# Analog.net
KiCad netlist of a schematic drawn in Altium Designer
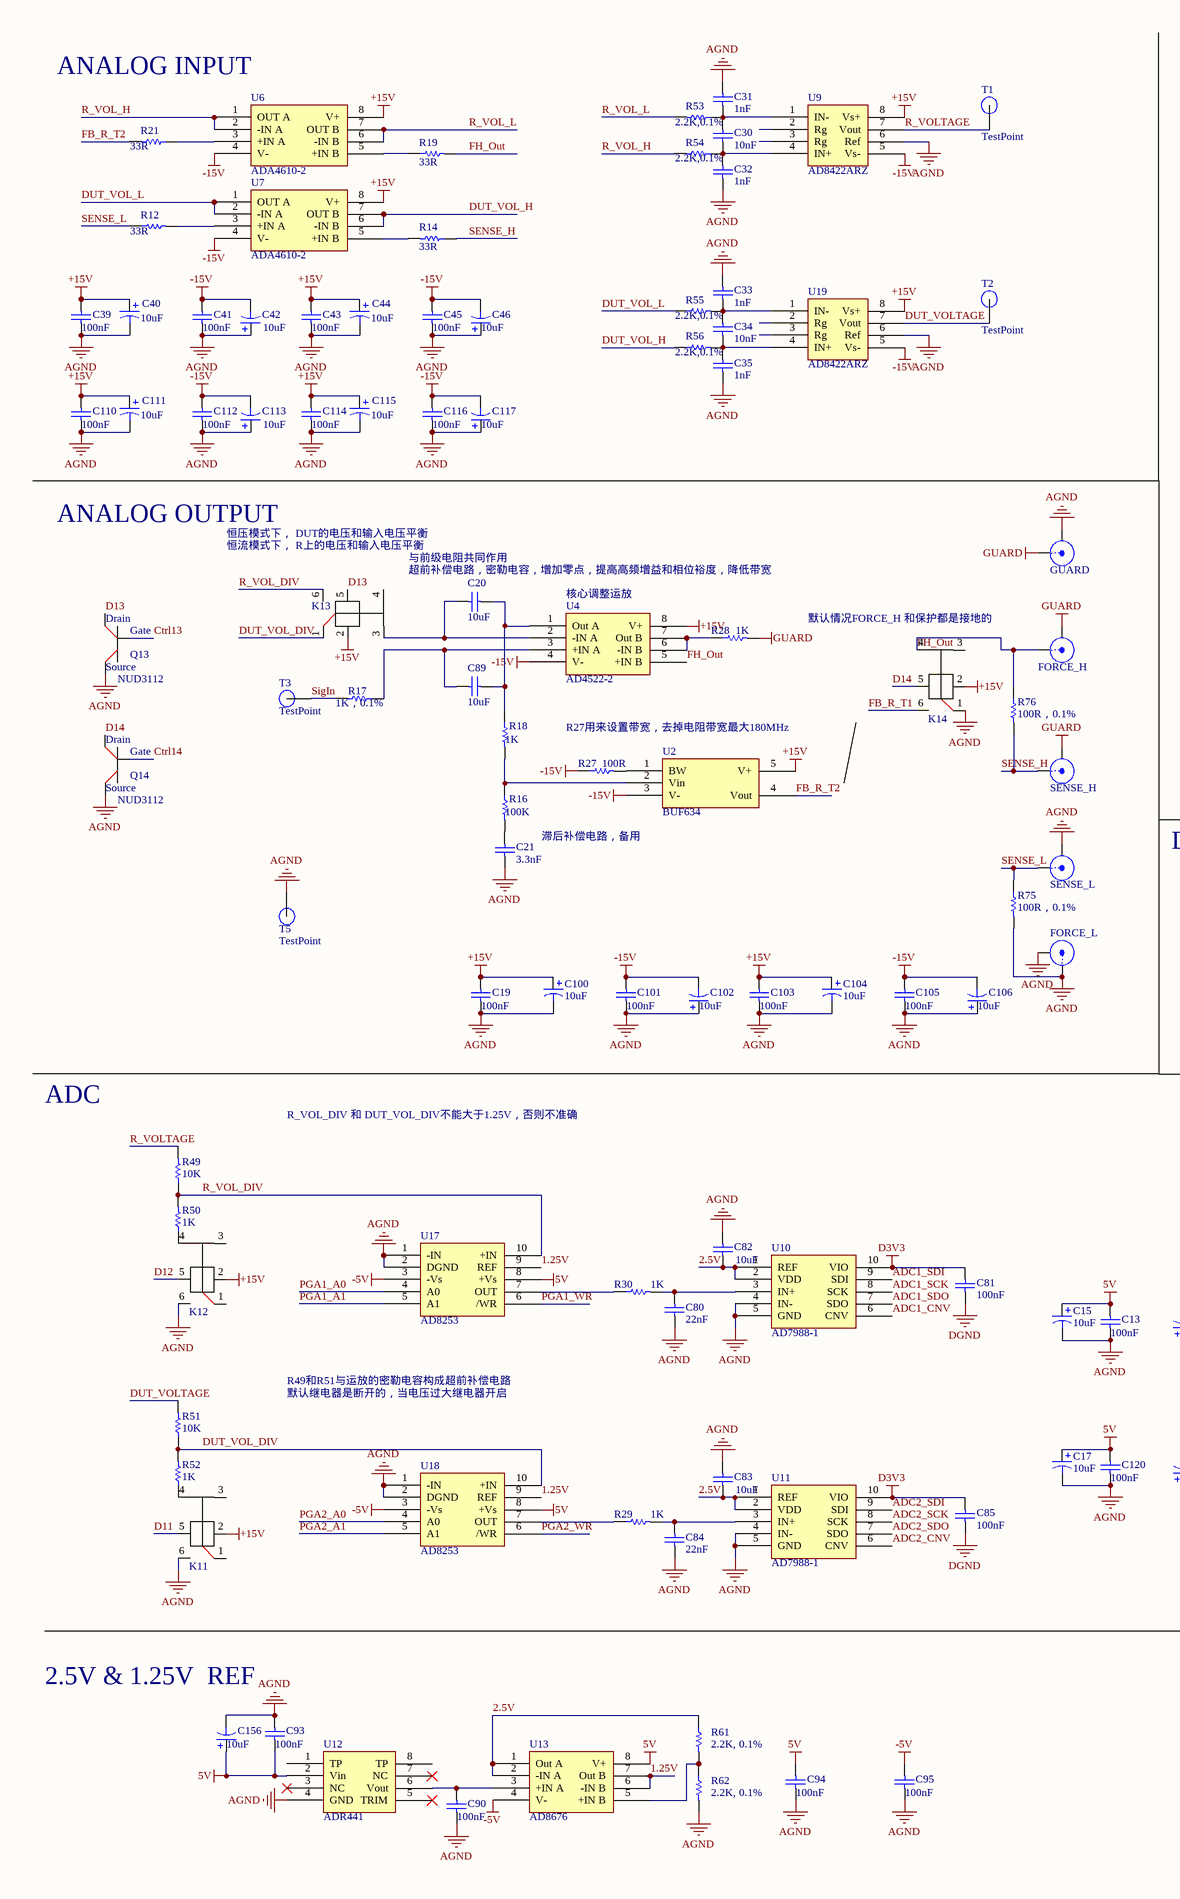
[diagram p0: Analog.SchDoc, left]
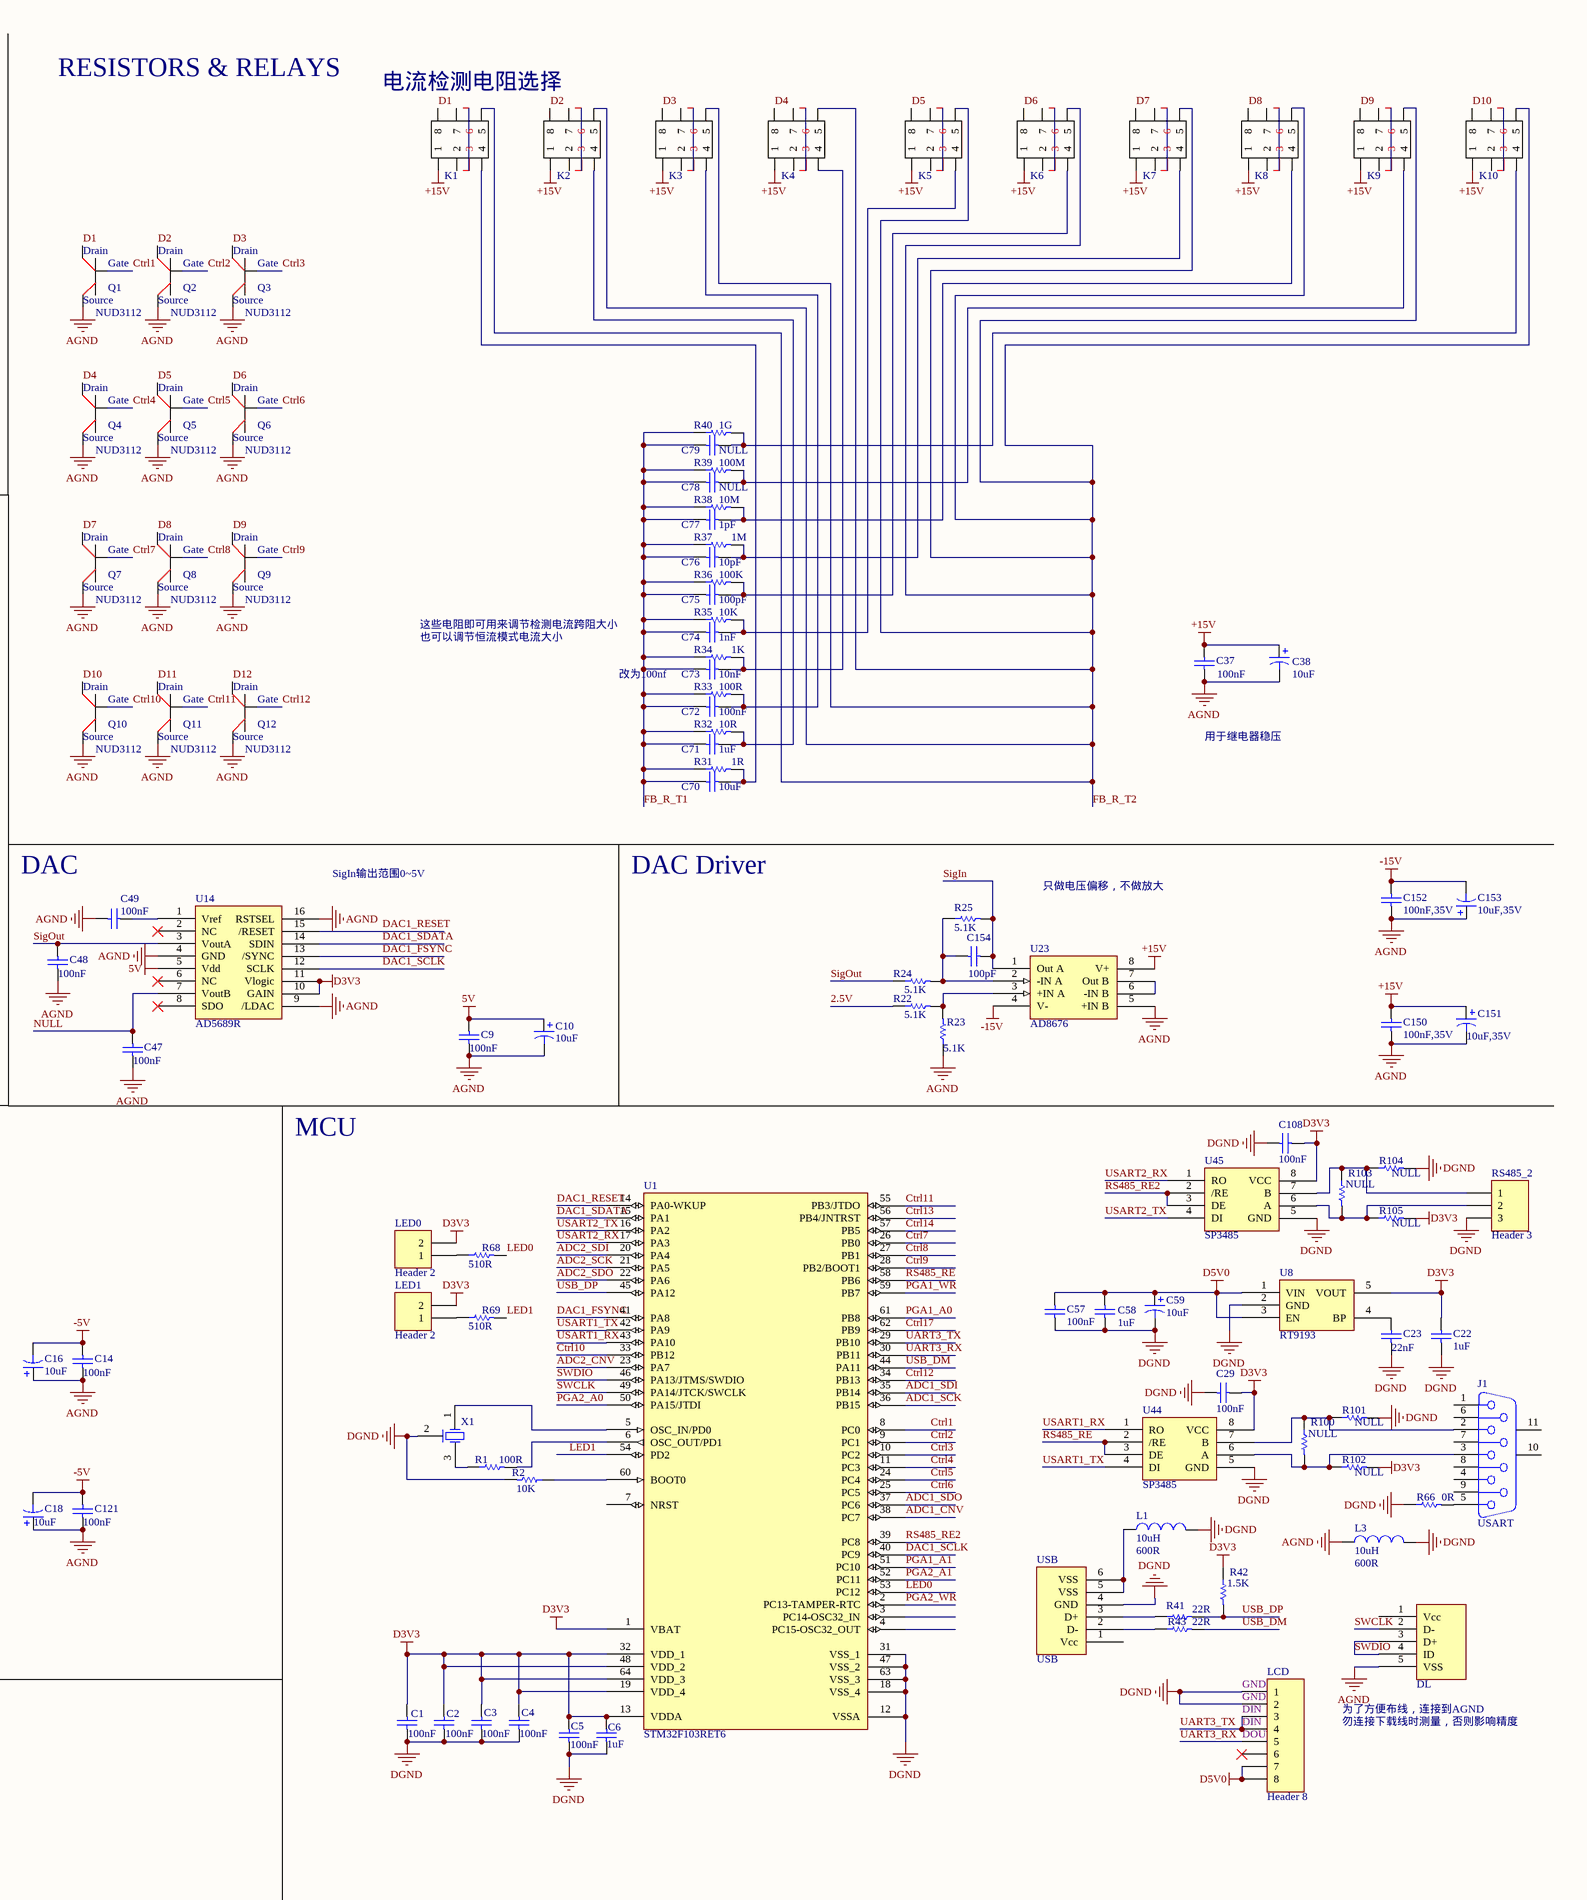
[diagram p1: Analog.SchDoc, right]

(export (version "E")
  (design (tool "Eeschema 10.0.6"))
  (components
    (comp (ref "C1")
      (value "100nF")
      (footprint "BinFeng:0603")
      (description "Capacitor")
      (fields (field (name "PUBLISHER") "Altium Limited"))
      (libsource (lib "Miscellaneous Devices") (part "Cap"))
    )
    (comp (ref "C2")
      (value "100nF")
      (footprint "BinFeng:0603")
      (description "Capacitor")
      (fields (field (name "PUBLISHER") "Altium Limited"))
      (libsource (lib "Miscellaneous Devices") (part "Cap"))
    )
    (comp (ref "C3")
      (value "100nF")
      (footprint "BinFeng:0603")
      (description "Capacitor")
      (fields (field (name "PUBLISHER") "Altium Limited"))
      (libsource (lib "Miscellaneous Devices") (part "Cap"))
    )
    (comp (ref "C4")
      (value "100nF")
      (footprint "BinFeng:0603")
      (description "Capacitor")
      (fields (field (name "PUBLISHER") "Altium Limited"))
      (libsource (lib "Miscellaneous Devices") (part "Cap"))
    )
    (comp (ref "C5")
      (value "100nF")
      (footprint "BinFeng:0603")
      (description "Capacitor")
      (fields (field (name "PUBLISHER") "Altium Limited"))
      (libsource (lib "Miscellaneous Devices") (part "Cap"))
    )
    (comp (ref "C6")
      (value "1uF")
      (footprint "BinFeng:0603")
      (description "Capacitor")
      (fields (field (name "PUBLISHER") "Altium Limited"))
      (libsource (lib "Miscellaneous Devices") (part "Cap"))
    )
    (comp (ref "C9")
      (value "100nF")
      (footprint "BinFeng:0603")
      (description "Capacitor")
      (fields (field (name "PUBLISHER") "Altium Limited"))
      (libsource (lib "Miscellaneous Devices") (part "Cap"))
    )
    (comp (ref "C10")
      (value "10uF")
      (footprint "3216")
      (description "Polarized Capacitor (Radial)")
      (fields (field (name "PUBLISHER") "Altium Limited"))
      (libsource (lib "Miscellaneous Devices") (part "Cap Pol1"))
    )
    (comp (ref "C13")
      (value "100nF")
      (footprint "BinFeng:0603")
      (description "Capacitor")
      (fields (field (name "PUBLISHER") "Altium Limited"))
      (libsource (lib "Miscellaneous Devices") (part "Cap"))
    )
    (comp (ref "C14")
      (value "100nF")
      (footprint "BinFeng:0603")
      (description "Capacitor")
      (fields (field (name "PUBLISHER") "Altium Limited"))
      (libsource (lib "Miscellaneous Devices") (part "Cap"))
    )
    (comp (ref "C15")
      (value "10uF")
      (footprint "3216")
      (description "Polarized Capacitor (Radial)")
      (fields (field (name "PUBLISHER") "Altium Limited"))
      (libsource (lib "Miscellaneous Devices") (part "Cap Pol1"))
    )
    (comp (ref "C16")
      (value "10uF")
      (footprint "3216")
      (description "Polarized Capacitor (Radial)")
      (fields (field (name "PUBLISHER") "Altium Limited"))
      (libsource (lib "Miscellaneous Devices") (part "Cap Pol1"))
    )
    (comp (ref "C17")
      (value "10uF")
      (footprint "3216")
      (description "Polarized Capacitor (Radial)")
      (fields (field (name "PUBLISHER") "Altium Limited"))
      (libsource (lib "Miscellaneous Devices") (part "Cap Pol1"))
    )
    (comp (ref "C18")
      (value "10uF")
      (footprint "3216")
      (description "Polarized Capacitor (Radial)")
      (fields (field (name "PUBLISHER") "Altium Limited"))
      (libsource (lib "Miscellaneous Devices") (part "Cap Pol1"))
    )
    (comp (ref "C19")
      (value "100nF")
      (footprint "BinFeng:0603")
      (description "Capacitor")
      (fields (field (name "PUBLISHER") "Altium Limited"))
      (libsource (lib "Miscellaneous Devices") (part "Cap"))
    )
    (comp (ref "C20")
      (value "10uF")
      (footprint "0805")
      (description "Capacitor")
      (fields (field (name "PUBLISHER") "Altium Limited"))
      (libsource (lib "Miscellaneous Devices") (part "Cap"))
    )
    (comp (ref "C21")
      (value "3.3nF")
      (footprint "BinFeng:0603")
      (description "Capacitor")
      (fields (field (name "PUBLISHER") "Altium Limited"))
      (libsource (lib "Miscellaneous Devices") (part "Cap"))
    )
    (comp (ref "C22")
      (value "1uF")
      (footprint "BinFeng:0603")
      (description "Capacitor")
      (fields (field (name "PUBLISHER") "Altium Limited"))
      (libsource (lib "Miscellaneous Devices") (part "Cap"))
    )
    (comp (ref "C23")
      (value "22nF")
      (footprint "BinFeng:0603")
      (description "Capacitor")
      (fields (field (name "PUBLISHER") "Altium Limited"))
      (libsource (lib "Miscellaneous Devices") (part "Cap"))
    )
    (comp (ref "C29")
      (value "100nF")
      (footprint "BinFeng:0603")
      (description "Capacitor")
      (fields (field (name "PUBLISHER") "Altium Limited"))
      (libsource (lib "Miscellaneous Devices") (part "Cap"))
    )
    (comp (ref "C30")
      (value "10nF")
      (footprint "BinFeng:0603")
      (description "Capacitor")
      (fields (field (name "PUBLISHER") "Altium Limited"))
      (libsource (lib "Miscellaneous Devices") (part "Cap"))
    )
    (comp (ref "C31")
      (value "1nF")
      (footprint "BinFeng:0603")
      (description "Capacitor")
      (fields (field (name "PUBLISHER") "Altium Limited"))
      (libsource (lib "Miscellaneous Devices") (part "Cap"))
    )
    (comp (ref "C32")
      (value "1nF")
      (footprint "BinFeng:0603")
      (description "Capacitor")
      (fields (field (name "PUBLISHER") "Altium Limited"))
      (libsource (lib "Miscellaneous Devices") (part "Cap"))
    )
    (comp (ref "C33")
      (value "1nF")
      (footprint "BinFeng:0603")
      (description "Capacitor")
      (fields (field (name "PUBLISHER") "Altium Limited"))
      (libsource (lib "Miscellaneous Devices") (part "Cap"))
    )
    (comp (ref "C34")
      (value "10nF")
      (footprint "BinFeng:0603")
      (description "Capacitor")
      (fields (field (name "PUBLISHER") "Altium Limited"))
      (libsource (lib "Miscellaneous Devices") (part "Cap"))
    )
    (comp (ref "C35")
      (value "1nF")
      (footprint "BinFeng:0603")
      (description "Capacitor")
      (fields (field (name "PUBLISHER") "Altium Limited"))
      (libsource (lib "Miscellaneous Devices") (part "Cap"))
    )
    (comp (ref "C37")
      (value "100nF")
      (footprint "BinFeng:0603")
      (description "Capacitor")
      (fields (field (name "PUBLISHER") "Altium Limited"))
      (libsource (lib "Miscellaneous Devices") (part "Cap"))
    )
    (comp (ref "C38")
      (value "10uF")
      (footprint "3216")
      (description "Polarized Capacitor (Radial)")
      (fields (field (name "PUBLISHER") "Altium Limited"))
      (libsource (lib "Miscellaneous Devices") (part "Cap Pol1"))
    )
    (comp (ref "C39")
      (value "100nF")
      (footprint "BinFeng:0603")
      (description "Capacitor")
      (fields (field (name "PUBLISHER") "Altium Limited"))
      (libsource (lib "Miscellaneous Devices") (part "Cap"))
    )
    (comp (ref "C40")
      (value "10uF")
      (footprint "3216")
      (description "Polarized Capacitor (Radial)")
      (fields (field (name "PUBLISHER") "Altium Limited"))
      (libsource (lib "Miscellaneous Devices") (part "Cap Pol1"))
    )
    (comp (ref "C41")
      (value "100nF")
      (footprint "BinFeng:0603")
      (description "Capacitor")
      (fields (field (name "PUBLISHER") "Altium Limited"))
      (libsource (lib "Miscellaneous Devices") (part "Cap"))
    )
    (comp (ref "C42")
      (value "10uF")
      (footprint "3216")
      (description "Polarized Capacitor (Radial)")
      (fields (field (name "PUBLISHER") "Altium Limited"))
      (libsource (lib "Miscellaneous Devices") (part "Cap Pol1"))
    )
    (comp (ref "C43")
      (value "100nF")
      (footprint "BinFeng:0603")
      (description "Capacitor")
      (fields (field (name "PUBLISHER") "Altium Limited"))
      (libsource (lib "Miscellaneous Devices") (part "Cap"))
    )
    (comp (ref "C44")
      (value "10uF")
      (footprint "3216")
      (description "Polarized Capacitor (Radial)")
      (fields (field (name "PUBLISHER") "Altium Limited"))
      (libsource (lib "Miscellaneous Devices") (part "Cap Pol1"))
    )
    (comp (ref "C45")
      (value "100nF")
      (footprint "BinFeng:0603")
      (description "Capacitor")
      (fields (field (name "PUBLISHER") "Altium Limited"))
      (libsource (lib "Miscellaneous Devices") (part "Cap"))
    )
    (comp (ref "C46")
      (value "10uF")
      (footprint "3216")
      (description "Polarized Capacitor (Radial)")
      (fields (field (name "PUBLISHER") "Altium Limited"))
      (libsource (lib "Miscellaneous Devices") (part "Cap Pol1"))
    )
    (comp (ref "C47")
      (value "100nF")
      (footprint "BinFeng:0603")
      (description "Capacitor")
      (fields (field (name "PUBLISHER") "Altium Limited"))
      (libsource (lib "Miscellaneous Devices") (part "Cap"))
    )
    (comp (ref "C48")
      (value "100nF")
      (footprint "BinFeng:0603")
      (description "Capacitor")
      (fields (field (name "PUBLISHER") "Altium Limited"))
      (libsource (lib "Miscellaneous Devices") (part "Cap"))
    )
    (comp (ref "C49")
      (value "100nF")
      (footprint "BinFeng:0603")
      (description "Capacitor")
      (fields (field (name "PUBLISHER") "Altium Limited"))
      (libsource (lib "Miscellaneous Devices") (part "Cap"))
    )
    (comp (ref "C57")
      (value "100nF")
      (footprint "0805")
      (description "Capacitor,100V")
      (fields (field (name "PUBLISHER") "Altium Limited"))
      (libsource (lib "Miscellaneous Devices") (part "Cap"))
    )
    (comp (ref "C58")
      (value "1uF")
      (footprint "0805")
      (description "Capacitor")
      (fields (field (name "PUBLISHER") "Altium Limited"))
      (libsource (lib "Miscellaneous Devices") (part "Cap"))
    )
    (comp (ref "C59")
      (value "10uF")
      (footprint "6032_pol")
      (description "Polarized Capacitor (Radial)")
      (fields (field (name "PUBLISHER") "Altium Limited"))
      (libsource (lib "Miscellaneous Devices") (part "Cap Pol1"))
    )
    (comp (ref "C70")
      (value "10uF")
      (footprint "0805")
      (description "Capacitor")
      (fields (field (name "PUBLISHER") "Altium Limited"))
      (libsource (lib "Miscellaneous Devices") (part "Cap"))
    )
    (comp (ref "C71")
      (value "1uF")
      (footprint "0805")
      (description "Capacitor")
      (fields (field (name "PUBLISHER") "Altium Limited"))
      (libsource (lib "Miscellaneous Devices") (part "Cap"))
    )
    (comp (ref "C72")
      (value "100nF")
      (footprint "0805")
      (description "Capacitor")
      (fields (field (name "PUBLISHER") "Altium Limited"))
      (libsource (lib "Miscellaneous Devices") (part "Cap"))
    )
    (comp (ref "C73")
      (value "10nF")
      (footprint "0805")
      (description "Capacitor")
      (fields (field (name "PUBLISHER") "Altium Limited"))
      (libsource (lib "Miscellaneous Devices") (part "Cap"))
    )
    (comp (ref "C74")
      (value "1nF")
      (footprint "0805")
      (description "Capacitor")
      (fields (field (name "PUBLISHER") "Altium Limited"))
      (libsource (lib "Miscellaneous Devices") (part "Cap"))
    )
    (comp (ref "C75")
      (value "100pF")
      (footprint "0805")
      (description "Capacitor")
      (fields (field (name "PUBLISHER") "Altium Limited"))
      (libsource (lib "Miscellaneous Devices") (part "Cap"))
    )
    (comp (ref "C76")
      (value "10pF")
      (footprint "0805")
      (description "Capacitor")
      (fields (field (name "PUBLISHER") "Altium Limited"))
      (libsource (lib "Miscellaneous Devices") (part "Cap"))
    )
    (comp (ref "C77")
      (value "1pF")
      (footprint "0805")
      (description "Capacitor")
      (fields (field (name "PUBLISHER") "Altium Limited"))
      (libsource (lib "Miscellaneous Devices") (part "Cap"))
    )
    (comp (ref "C78")
      (value "NULL")
      (footprint "0805")
      (description "Capacitor")
      (fields (field (name "PUBLISHER") "Altium Limited"))
      (libsource (lib "Miscellaneous Devices") (part "Cap"))
    )
    (comp (ref "C79")
      (value "NULL")
      (footprint "0805")
      (description "Capacitor")
      (fields (field (name "PUBLISHER") "Altium Limited"))
      (libsource (lib "Miscellaneous Devices") (part "Cap"))
    )
    (comp (ref "C80")
      (value "22nF")
      (footprint "BinFeng:0603")
      (description "Capacitor")
      (fields (field (name "PUBLISHER") "Altium Limited"))
      (libsource (lib "Miscellaneous Devices") (part "Cap"))
    )
    (comp (ref "C81")
      (value "100nF")
      (footprint "BinFeng:0603")
      (description "Capacitor,100V")
      (fields (field (name "PUBLISHER") "Altium Limited"))
      (libsource (lib "Miscellaneous Devices") (part "Cap"))
    )
    (comp (ref "C82")
      (value "10uF")
      (footprint "0805")
      (description "Capacitor")
      (fields (field (name "PUBLISHER") "Altium Limited"))
      (libsource (lib "Miscellaneous Devices") (part "Cap"))
    )
    (comp (ref "C83")
      (value "10uF")
      (footprint "0805")
      (description "Capacitor")
      (fields (field (name "PUBLISHER") "Altium Limited"))
      (libsource (lib "Miscellaneous Devices") (part "Cap"))
    )
    (comp (ref "C84")
      (value "22nF")
      (footprint "BinFeng:0603")
      (description "Capacitor")
      (fields (field (name "PUBLISHER") "Altium Limited"))
      (libsource (lib "Miscellaneous Devices") (part "Cap"))
    )
    (comp (ref "C85")
      (value "100nF")
      (footprint "BinFeng:0603")
      (description "Capacitor,100V")
      (fields (field (name "PUBLISHER") "Altium Limited"))
      (libsource (lib "Miscellaneous Devices") (part "Cap"))
    )
    (comp (ref "C89")
      (value "10uF")
      (footprint "0805")
      (description "Capacitor")
      (fields (field (name "PUBLISHER") "Altium Limited"))
      (libsource (lib "Miscellaneous Devices") (part "Cap"))
    )
    (comp (ref "C90")
      (value "100nF")
      (footprint "BinFeng:0603")
      (description "Capacitor")
      (fields (field (name "PUBLISHER") "Altium Limited"))
      (libsource (lib "Miscellaneous Devices") (part "Cap"))
    )
    (comp (ref "C93")
      (value "100nF")
      (footprint "BinFeng:0603")
      (description "Capacitor")
      (fields (field (name "PUBLISHER") "Altium Limited"))
      (libsource (lib "Miscellaneous Devices") (part "Cap"))
    )
    (comp (ref "C94")
      (value "100nF")
      (footprint "BinFeng:0603")
      (description "Capacitor")
      (fields (field (name "PUBLISHER") "Altium Limited"))
      (libsource (lib "Miscellaneous Devices") (part "Cap"))
    )
    (comp (ref "C95")
      (value "100nF")
      (footprint "BinFeng:0603")
      (description "Capacitor")
      (fields (field (name "PUBLISHER") "Altium Limited"))
      (libsource (lib "Miscellaneous Devices") (part "Cap"))
    )
    (comp (ref "C100")
      (value "10uF")
      (footprint "3216")
      (description "Polarized Capacitor (Radial)")
      (fields (field (name "PUBLISHER") "Altium Limited"))
      (libsource (lib "Miscellaneous Devices") (part "Cap Pol1"))
    )
    (comp (ref "C101")
      (value "100nF")
      (footprint "BinFeng:0603")
      (description "Capacitor")
      (fields (field (name "PUBLISHER") "Altium Limited"))
      (libsource (lib "Miscellaneous Devices") (part "Cap"))
    )
    (comp (ref "C102")
      (value "10uF")
      (footprint "3216")
      (description "Polarized Capacitor (Radial)")
      (fields (field (name "PUBLISHER") "Altium Limited"))
      (libsource (lib "Miscellaneous Devices") (part "Cap Pol1"))
    )
    (comp (ref "C103")
      (value "100nF")
      (footprint "BinFeng:0603")
      (description "Capacitor")
      (fields (field (name "PUBLISHER") "Altium Limited"))
      (libsource (lib "Miscellaneous Devices") (part "Cap"))
    )
    (comp (ref "C104")
      (value "10uF")
      (footprint "3216")
      (description "Polarized Capacitor (Radial)")
      (fields (field (name "PUBLISHER") "Altium Limited"))
      (libsource (lib "Miscellaneous Devices") (part "Cap Pol1"))
    )
    (comp (ref "C105")
      (value "100nF")
      (footprint "BinFeng:0603")
      (description "Capacitor")
      (fields (field (name "PUBLISHER") "Altium Limited"))
      (libsource (lib "Miscellaneous Devices") (part "Cap"))
    )
    (comp (ref "C106")
      (value "10uF")
      (footprint "3216")
      (description "Polarized Capacitor (Radial)")
      (fields (field (name "PUBLISHER") "Altium Limited"))
      (libsource (lib "Miscellaneous Devices") (part "Cap Pol1"))
    )
    (comp (ref "C108")
      (value "100nF")
      (footprint "BinFeng:0603")
      (description "Capacitor")
      (fields (field (name "PUBLISHER") "Altium Limited"))
      (libsource (lib "Miscellaneous Devices") (part "Cap"))
    )
    (comp (ref "C110")
      (value "100nF")
      (footprint "BinFeng:0603")
      (description "Capacitor")
      (fields (field (name "PUBLISHER") "Altium Limited"))
      (libsource (lib "Miscellaneous Devices") (part "Cap"))
    )
    (comp (ref "C111")
      (value "10uF")
      (footprint "3216")
      (description "Polarized Capacitor (Radial)")
      (fields (field (name "PUBLISHER") "Altium Limited"))
      (libsource (lib "Miscellaneous Devices") (part "Cap Pol1"))
    )
    (comp (ref "C112")
      (value "100nF")
      (footprint "BinFeng:0603")
      (description "Capacitor")
      (fields (field (name "PUBLISHER") "Altium Limited"))
      (libsource (lib "Miscellaneous Devices") (part "Cap"))
    )
    (comp (ref "C113")
      (value "10uF")
      (footprint "3216")
      (description "Polarized Capacitor (Radial)")
      (fields (field (name "PUBLISHER") "Altium Limited"))
      (libsource (lib "Miscellaneous Devices") (part "Cap Pol1"))
    )
    (comp (ref "C114")
      (value "100nF")
      (footprint "BinFeng:0603")
      (description "Capacitor")
      (fields (field (name "PUBLISHER") "Altium Limited"))
      (libsource (lib "Miscellaneous Devices") (part "Cap"))
    )
    (comp (ref "C115")
      (value "10uF")
      (footprint "3216")
      (description "Polarized Capacitor (Radial)")
      (fields (field (name "PUBLISHER") "Altium Limited"))
      (libsource (lib "Miscellaneous Devices") (part "Cap Pol1"))
    )
    (comp (ref "C116")
      (value "100nF")
      (footprint "BinFeng:0603")
      (description "Capacitor")
      (fields (field (name "PUBLISHER") "Altium Limited"))
      (libsource (lib "Miscellaneous Devices") (part "Cap"))
    )
    (comp (ref "C117")
      (value "10uF")
      (footprint "3216")
      (description "Polarized Capacitor (Radial)")
      (fields (field (name "PUBLISHER") "Altium Limited"))
      (libsource (lib "Miscellaneous Devices") (part "Cap Pol1"))
    )
    (comp (ref "C120")
      (value "100nF")
      (footprint "BinFeng:0603")
      (description "Capacitor")
      (fields (field (name "PUBLISHER") "Altium Limited"))
      (libsource (lib "Miscellaneous Devices") (part "Cap"))
    )
    (comp (ref "C121")
      (value "100nF")
      (footprint "BinFeng:0603")
      (description "Capacitor")
      (fields (field (name "PUBLISHER") "Altium Limited"))
      (libsource (lib "Miscellaneous Devices") (part "Cap"))
    )
    (comp (ref "C150")
      (value "100nF,35V")
      (footprint "BinFeng:0603")
      (description "Capacitor")
      (fields (field (name "Comment") "100nF") (field (name "PUBLISHER") "Altium Limited"))
      (libsource (lib "Miscellaneous Devices") (part "Cap"))
    )
    (comp (ref "C151")
      (value "10uF,35V")
      (footprint "3216")
      (description "Polarized Capacitor (Radial)")
      (fields (field (name "Comment") "10uF") (field (name "PUBLISHER") "Altium Limited"))
      (libsource (lib "Miscellaneous Devices") (part "Cap Pol1"))
    )
    (comp (ref "C152")
      (value "100nF,35V")
      (footprint "BinFeng:0603")
      (description "Capacitor")
      (fields (field (name "Comment") "100nF") (field (name "PUBLISHER") "Altium Limited"))
      (libsource (lib "Miscellaneous Devices") (part "Cap"))
    )
    (comp (ref "C153")
      (value "10uF,35V")
      (footprint "3216")
      (description "Polarized Capacitor (Radial)")
      (fields (field (name "Comment") "10uF") (field (name "PUBLISHER") "Altium Limited"))
      (libsource (lib "Miscellaneous Devices") (part "Cap Pol1"))
    )
    (comp (ref "C154")
      (value "100pF")
      (footprint "0805")
      (description "Capacitor")
      (fields (field (name "PUBLISHER") "Altium Limited"))
      (libsource (lib "Miscellaneous Devices") (part "Cap"))
    )
    (comp (ref "C156")
      (value "10uF")
      (footprint "3216")
      (description "Polarized Capacitor (Radial)")
      (fields (field (name "PUBLISHER") "Altium Limited"))
      (libsource (lib "Miscellaneous Devices") (part "Cap Pol1"))
    )
    (comp (ref "DL")
      (value "USB_5pin")
      (footprint "USBmicro_B")
      (libsource (lib "BinFeng_Connectors") (part "USB_5pin"))
    )
    (comp (ref "FORCE_H")
      (value "SMB")
      (footprint "SMA")
      (description "SMB Straight Connector")
      (fields (field (name "PUBLISHER") "Altium Limited"))
      (libsource (lib "Miscellaneous Connectors") (part "SMB"))
    )
    (comp (ref "FORCE_L")
      (value "SMB")
      (footprint "SMA")
      (description "SMB Straight Connector")
      (fields (field (name "PUBLISHER") "Altium Limited"))
      (libsource (lib "Miscellaneous Connectors") (part "SMB"))
    )
    (comp (ref "GUARD")
      (value "SMB")
      (footprint "SMA")
      (description "SMB Straight Connector")
      (fields (field (name "PUBLISHER") "Altium Limited"))
      (libsource (lib "Miscellaneous Connectors") (part "SMB"))
    )
    (comp (ref "J1")
      (value "USART")
      (footprint "DSUB1.385-2H9")
      (description "Receptacle Assembly, 9 Position, Right Angle")
      (fields (field (name "PUBLISHER") "Altium Limited"))
      (libsource (lib "Miscellaneous Connectors") (part "D Connector 9"))
    )
    (comp (ref "K1")
      (value "AXICOM IM")
      (footprint "AXICOM_IM06")
      (libsource (lib "BinFeng_IC") (part "AXiCOM IM05"))
    )
    (comp (ref "K2")
      (value "AXICOM IM")
      (footprint "AXICOM_IM06")
      (libsource (lib "BinFeng_IC") (part "AXiCOM IM05"))
    )
    (comp (ref "K3")
      (value "AXICOM IM")
      (footprint "AXICOM_IM06")
      (libsource (lib "BinFeng_IC") (part "AXiCOM IM05"))
    )
    (comp (ref "K4")
      (value "AXICOM IM")
      (footprint "AXICOM_IM06")
      (libsource (lib "BinFeng_IC") (part "AXiCOM IM05"))
    )
    (comp (ref "K5")
      (value "AXICOM IM")
      (footprint "AXICOM_IM06")
      (libsource (lib "BinFeng_IC") (part "AXiCOM IM05"))
    )
    (comp (ref "K6")
      (value "AXICOM IM")
      (footprint "AXICOM_IM06")
      (libsource (lib "BinFeng_IC") (part "AXiCOM IM05"))
    )
    (comp (ref "K7")
      (value "AXICOM IM")
      (footprint "AXICOM_IM06")
      (libsource (lib "BinFeng_IC") (part "AXiCOM IM05"))
    )
    (comp (ref "K8")
      (value "AXICOM IM")
      (footprint "AXICOM_IM06")
      (libsource (lib "BinFeng_IC") (part "AXiCOM IM05"))
    )
    (comp (ref "K9")
      (value "AXICOM IM")
      (footprint "AXICOM_IM06")
      (libsource (lib "BinFeng_IC") (part "AXiCOM IM05"))
    )
    (comp (ref "K10")
      (value "AXICOM IM")
      (footprint "AXICOM_IM06")
      (libsource (lib "BinFeng_IC") (part "AXiCOM IM05"))
    )
    (comp (ref "K11")
      (value "Relay")
      (footprint "Relay_OMRON5V")
      (description "Relay OMRON")
      (libsource (lib "BinFeng_IC") (part "Relay_OMRON5V"))
    )
    (comp (ref "K12")
      (value "Relay")
      (footprint "Relay_OMRON5V")
      (description "Relay OMRON")
      (libsource (lib "BinFeng_IC") (part "Relay_OMRON5V"))
    )
    (comp (ref "K13")
      (value "Relay")
      (footprint "Relay_OMRON5V")
      (description "Relay OMRON")
      (libsource (lib "BinFeng_IC") (part "Relay_OMRON5V"))
    )
    (comp (ref "K14")
      (value "Relay")
      (footprint "Relay_OMRON5V")
      (description "Relay OMRON")
      (libsource (lib "BinFeng_IC") (part "Relay_OMRON5V"))
    )
    (comp (ref "L1")
      (value "10uH")
      (footprint "0805")
      (description "Inductor")
      (fields (field (name "ALTIUM_VALUE") "600R") (field (name "PUBLISHER") "Altium Limited"))
      (libsource (lib "Miscellaneous Devices") (part "Inductor"))
    )
    (comp (ref "L3")
      (value "10uH")
      (footprint "1206")
      (description "Inductor")
      (fields (field (name "ALTIUM_VALUE") "600R") (field (name "PUBLISHER") "Altium Limited"))
      (libsource (lib "Miscellaneous Devices") (part "Inductor"))
    )
    (comp (ref "LCD")
      (value "Header 8")
      (footprint "HDR1X8")
      (description "Header, 8-Pin")
      (fields (field (name "PUBLISHER") "Altium Limited"))
      (libsource (lib "Miscellaneous Connectors") (part "Header 8"))
    )
    (comp (ref "LED0")
      (value "Header 2")
      (footprint "HDR1X2")
      (description "Header, 2-Pin")
      (fields (field (name "PUBLISHER") "Altium Limited"))
      (libsource (lib "Miscellaneous Connectors") (part "Header 2"))
    )
    (comp (ref "LED1")
      (value "Header 2")
      (footprint "HDR1X2")
      (description "Header, 2-Pin")
      (fields (field (name "PUBLISHER") "Altium Limited"))
      (libsource (lib "Miscellaneous Connectors") (part "Header 2"))
    )
    (comp (ref "Q1")
      (value "NUD3112")
      (footprint "SOT23")
      (description "Relay Driver 5V Supply")
      (libsource (lib "BinFeng_IC") (part "NUD3105"))
    )
    (comp (ref "Q2")
      (value "NUD3112")
      (footprint "SOT23")
      (description "Relay Driver 5V Supply")
      (libsource (lib "BinFeng_IC") (part "NUD3105"))
    )
    (comp (ref "Q3")
      (value "NUD3112")
      (footprint "SOT23")
      (description "Relay Driver 5V Supply")
      (libsource (lib "BinFeng_IC") (part "NUD3105"))
    )
    (comp (ref "Q4")
      (value "NUD3112")
      (footprint "SOT23")
      (description "Relay Driver 5V Supply")
      (libsource (lib "BinFeng_IC") (part "NUD3105"))
    )
    (comp (ref "Q5")
      (value "NUD3112")
      (footprint "SOT23")
      (description "Relay Driver 5V Supply")
      (libsource (lib "BinFeng_IC") (part "NUD3105"))
    )
    (comp (ref "Q6")
      (value "NUD3112")
      (footprint "SOT23")
      (description "Relay Driver 5V Supply")
      (libsource (lib "BinFeng_IC") (part "NUD3105"))
    )
    (comp (ref "Q7")
      (value "NUD3112")
      (footprint "SOT23")
      (description "Relay Driver 5V Supply")
      (libsource (lib "BinFeng_IC") (part "NUD3105"))
    )
    (comp (ref "Q8")
      (value "NUD3112")
      (footprint "SOT23")
      (description "Relay Driver 5V Supply")
      (libsource (lib "BinFeng_IC") (part "NUD3105"))
    )
    (comp (ref "Q9")
      (value "NUD3112")
      (footprint "SOT23")
      (description "Relay Driver 5V Supply")
      (libsource (lib "BinFeng_IC") (part "NUD3105"))
    )
    (comp (ref "Q10")
      (value "NUD3112")
      (footprint "SOT23")
      (description "Relay Driver 5V Supply")
      (libsource (lib "BinFeng_IC") (part "NUD3105"))
    )
    (comp (ref "Q11")
      (value "NUD3112")
      (footprint "SOT23")
      (description "Relay Driver 5V Supply")
      (libsource (lib "BinFeng_IC") (part "NUD3105"))
    )
    (comp (ref "Q12")
      (value "NUD3112")
      (footprint "SOT23")
      (description "Relay Driver 5V Supply")
      (libsource (lib "BinFeng_IC") (part "NUD3105"))
    )
    (comp (ref "Q13")
      (value "NUD3112")
      (footprint "SOT23")
      (description "Relay Driver 5V Supply")
      (libsource (lib "BinFeng_IC") (part "NUD3105"))
    )
    (comp (ref "Q14")
      (value "NUD3112")
      (footprint "SOT23")
      (description "Relay Driver 5V Supply")
      (libsource (lib "BinFeng_IC") (part "NUD3105"))
    )
    (comp (ref "R1")
      (value "100R")
      (footprint "BinFeng:0603")
      (description "Resistor")
      (fields (field (name "PUBLISHER") "Altium Limited"))
      (libsource (lib "Miscellaneous Devices") (part "Res1"))
    )
    (comp (ref "R2")
      (value "10K")
      (footprint "BinFeng:0603")
      (description "Resistor")
      (fields (field (name "PUBLISHER") "Altium Limited"))
      (libsource (lib "Miscellaneous Devices") (part "Res1"))
    )
    (comp (ref "R12")
      (value "33R")
      (footprint "BinFeng:0603")
      (description "Resistor")
      (fields (field (name "PUBLISHER") "Altium Limited"))
      (libsource (lib "Miscellaneous Devices") (part "Res1"))
    )
    (comp (ref "R14")
      (value "33R")
      (footprint "BinFeng:0603")
      (description "Resistor")
      (fields (field (name "PUBLISHER") "Altium Limited"))
      (libsource (lib "Miscellaneous Devices") (part "Res1"))
    )
    (comp (ref "R16")
      (value "100K")
      (footprint "BinFeng:0603")
      (description "Resistor")
      (fields (field (name "PUBLISHER") "Altium Limited"))
      (libsource (lib "Miscellaneous Devices") (part "Res1"))
    )
    (comp (ref "R17")
      (value "1K，0.1%")
      (footprint "BinFeng:0603")
      (description "Resistor")
      (fields (field (name "PUBLISHER") "Altium Limited"))
      (libsource (lib "Miscellaneous Devices") (part "Res1"))
    )
    (comp (ref "R18")
      (value "1K")
      (footprint "BinFeng:0603")
      (description "Resistor")
      (fields (field (name "PUBLISHER") "Altium Limited"))
      (libsource (lib "Miscellaneous Devices") (part "Res1"))
    )
    (comp (ref "R19")
      (value "33R")
      (footprint "BinFeng:0603")
      (description "Resistor")
      (fields (field (name "PUBLISHER") "Altium Limited"))
      (libsource (lib "Miscellaneous Devices") (part "Res1"))
    )
    (comp (ref "R21")
      (value "33R")
      (footprint "BinFeng:0603")
      (description "Resistor")
      (fields (field (name "PUBLISHER") "Altium Limited"))
      (libsource (lib "Miscellaneous Devices") (part "Res1"))
    )
    (comp (ref "R22")
      (value "5.1K")
      (footprint "0805")
      (description "Resistor")
      (fields (field (name "PUBLISHER") "Altium Limited"))
      (libsource (lib "Miscellaneous Devices") (part "Res1"))
    )
    (comp (ref "R23")
      (value "5.1K")
      (footprint "0805")
      (description "Resistor")
      (fields (field (name "PUBLISHER") "Altium Limited"))
      (libsource (lib "Miscellaneous Devices") (part "Res1"))
    )
    (comp (ref "R24")
      (value "5.1K")
      (footprint "0805")
      (description "Resistor")
      (fields (field (name "PUBLISHER") "Altium Limited"))
      (libsource (lib "Miscellaneous Devices") (part "Res1"))
    )
    (comp (ref "R25")
      (value "5.1K")
      (footprint "0805")
      (description "Resistor")
      (fields (field (name "PUBLISHER") "Altium Limited"))
      (libsource (lib "Miscellaneous Devices") (part "Res1"))
    )
    (comp (ref "R27")
      (value "100R")
      (footprint "BinFeng:0603")
      (description "Resistor")
      (fields (field (name "PUBLISHER") "Altium Limited"))
      (libsource (lib "Miscellaneous Devices") (part "Res1"))
    )
    (comp (ref "R28")
      (value "1K")
      (footprint "BinFeng:0603")
      (description "Resistor")
      (fields (field (name "PUBLISHER") "Altium Limited"))
      (libsource (lib "Miscellaneous Devices") (part "Res1"))
    )
    (comp (ref "R29")
      (value "1K")
      (footprint "BinFeng:0603")
      (description "Resistor")
      (fields (field (name "PUBLISHER") "Altium Limited"))
      (libsource (lib "Miscellaneous Devices") (part "Res1"))
    )
    (comp (ref "R30")
      (value "1K")
      (footprint "BinFeng:0603")
      (description "Resistor")
      (fields (field (name "PUBLISHER") "Altium Limited"))
      (libsource (lib "Miscellaneous Devices") (part "Res1"))
    )
    (comp (ref "R31")
      (value "1R")
      (footprint "0805")
      (description "Resistor")
      (fields (field (name "PUBLISHER") "Altium Limited"))
      (libsource (lib "Miscellaneous Devices") (part "Res1"))
    )
    (comp (ref "R32")
      (value "10R")
      (footprint "0805")
      (description "Resistor")
      (fields (field (name "PUBLISHER") "Altium Limited"))
      (libsource (lib "Miscellaneous Devices") (part "Res1"))
    )
    (comp (ref "R33")
      (value "100R")
      (footprint "0805")
      (description "Resistor")
      (fields (field (name "PUBLISHER") "Altium Limited"))
      (libsource (lib "Miscellaneous Devices") (part "Res1"))
    )
    (comp (ref "R34")
      (value "1K")
      (footprint "0805")
      (description "Resistor")
      (fields (field (name "PUBLISHER") "Altium Limited"))
      (libsource (lib "Miscellaneous Devices") (part "Res1"))
    )
    (comp (ref "R35")
      (value "10K")
      (footprint "0805")
      (description "Resistor")
      (fields (field (name "PUBLISHER") "Altium Limited"))
      (libsource (lib "Miscellaneous Devices") (part "Res1"))
    )
    (comp (ref "R36")
      (value "100K")
      (footprint "0805")
      (description "Resistor")
      (fields (field (name "PUBLISHER") "Altium Limited"))
      (libsource (lib "Miscellaneous Devices") (part "Res1"))
    )
    (comp (ref "R37")
      (value "1M")
      (footprint "0805")
      (description "Resistor")
      (fields (field (name "PUBLISHER") "Altium Limited"))
      (libsource (lib "Miscellaneous Devices") (part "Res1"))
    )
    (comp (ref "R38")
      (value "10M")
      (footprint "0805")
      (description "Resistor")
      (fields (field (name "PUBLISHER") "Altium Limited"))
      (libsource (lib "Miscellaneous Devices") (part "Res1"))
    )
    (comp (ref "R39")
      (value "100M")
      (footprint "0805")
      (description "Resistor")
      (fields (field (name "PUBLISHER") "Altium Limited"))
      (libsource (lib "Miscellaneous Devices") (part "Res1"))
    )
    (comp (ref "R40")
      (value "1G")
      (footprint "0805")
      (description "Resistor")
      (fields (field (name "PUBLISHER") "Altium Limited"))
      (libsource (lib "Miscellaneous Devices") (part "Res1"))
    )
    (comp (ref "R41")
      (value "22R")
      (footprint "BinFeng:0402")
      (description "Resistor")
      (fields (field (name "PUBLISHER") "Altium Limited"))
      (libsource (lib "Miscellaneous Devices") (part "Res1"))
    )
    (comp (ref "R42")
      (value "1.5K")
      (footprint "BinFeng:0402")
      (description "Resistor")
      (fields (field (name "PUBLISHER") "Altium Limited"))
      (libsource (lib "Miscellaneous Devices") (part "Res1"))
    )
    (comp (ref "R43")
      (value "22R")
      (footprint "BinFeng:0402")
      (description "Resistor")
      (fields (field (name "PUBLISHER") "Altium Limited"))
      (libsource (lib "Miscellaneous Devices") (part "Res1"))
    )
    (comp (ref "R49")
      (value "10K")
      (footprint "BinFeng:0603")
      (description "Resistor")
      (fields (field (name "PUBLISHER") "Altium Limited"))
      (libsource (lib "Miscellaneous Devices") (part "Res1"))
    )
    (comp (ref "R50")
      (value "1K")
      (footprint "BinFeng:0603")
      (description "Resistor")
      (fields (field (name "PUBLISHER") "Altium Limited"))
      (libsource (lib "Miscellaneous Devices") (part "Res1"))
    )
    (comp (ref "R51")
      (value "10K")
      (footprint "BinFeng:0603")
      (description "Resistor")
      (fields (field (name "PUBLISHER") "Altium Limited"))
      (libsource (lib "Miscellaneous Devices") (part "Res1"))
    )
    (comp (ref "R52")
      (value "1K")
      (footprint "BinFeng:0603")
      (description "Resistor")
      (fields (field (name "PUBLISHER") "Altium Limited"))
      (libsource (lib "Miscellaneous Devices") (part "Res1"))
    )
    (comp (ref "R53")
      (value "2.2K,0.1%")
      (footprint "BinFeng:0603")
      (description "Resistor")
      (fields (field (name "PUBLISHER") "Altium Limited"))
      (libsource (lib "Miscellaneous Devices") (part "Res1"))
    )
    (comp (ref "R54")
      (value "2.2K,0.1%")
      (footprint "BinFeng:0603")
      (description "Resistor")
      (fields (field (name "PUBLISHER") "Altium Limited"))
      (libsource (lib "Miscellaneous Devices") (part "Res1"))
    )
    (comp (ref "R55")
      (value "2.2K,0.1%")
      (footprint "BinFeng:0603")
      (description "Resistor")
      (fields (field (name "PUBLISHER") "Altium Limited"))
      (libsource (lib "Miscellaneous Devices") (part "Res1"))
    )
    (comp (ref "R56")
      (value "2.2K,0.1%")
      (footprint "BinFeng:0603")
      (description "Resistor")
      (fields (field (name "PUBLISHER") "Altium Limited"))
      (libsource (lib "Miscellaneous Devices") (part "Res1"))
    )
    (comp (ref "R61")
      (value "2.2K, 0.1%")
      (footprint "BinFeng:0603")
      (description "Resistor")
      (fields (field (name "PUBLISHER") "Altium Limited"))
      (libsource (lib "Miscellaneous Devices") (part "Res1"))
    )
    (comp (ref "R62")
      (value "2.2K, 0.1%")
      (footprint "BinFeng:0603")
      (description "Resistor")
      (fields (field (name "PUBLISHER") "Altium Limited"))
      (libsource (lib "Miscellaneous Devices") (part "Res1"))
    )
    (comp (ref "R66")
      (value "0R")
      (footprint "BinFeng:0402")
      (description "Resistor")
      (fields (field (name "PUBLISHER") "Altium Limited"))
      (libsource (lib "Miscellaneous Devices") (part "Res1"))
    )
    (comp (ref "R68")
      (value "510R")
      (footprint "BinFeng:0603")
      (description "Resistor")
      (fields (field (name "PUBLISHER") "Altium Limited"))
      (libsource (lib "Miscellaneous Devices") (part "Res1"))
    )
    (comp (ref "R69")
      (value "510R")
      (footprint "BinFeng:0603")
      (description "Resistor")
      (fields (field (name "PUBLISHER") "Altium Limited"))
      (libsource (lib "Miscellaneous Devices") (part "Res1"))
    )
    (comp (ref "R75")
      (value "100R，0.1%")
      (footprint "BinFeng:0603")
      (description "Resistor")
      (fields (field (name "PUBLISHER") "Altium Limited"))
      (libsource (lib "Miscellaneous Devices") (part "Res1"))
    )
    (comp (ref "R76")
      (value "100R，0.1%")
      (footprint "BinFeng:0603")
      (description "Resistor")
      (fields (field (name "PUBLISHER") "Altium Limited"))
      (libsource (lib "Miscellaneous Devices") (part "Res1"))
    )
    (comp (ref "R100")
      (value "NULL")
      (footprint "BinFeng:0603")
      (description "Resistor")
      (fields (field (name "PUBLISHER") "Altium Limited"))
      (libsource (lib "Miscellaneous Devices") (part "Res1"))
    )
    (comp (ref "R101")
      (value "NULL")
      (footprint "BinFeng:0603")
      (description "Resistor")
      (fields (field (name "PUBLISHER") "Altium Limited"))
      (libsource (lib "Miscellaneous Devices") (part "Res1"))
    )
    (comp (ref "R102")
      (value "NULL")
      (footprint "BinFeng:0603")
      (description "Resistor")
      (fields (field (name "PUBLISHER") "Altium Limited"))
      (libsource (lib "Miscellaneous Devices") (part "Res1"))
    )
    (comp (ref "R103")
      (value "NULL")
      (footprint "BinFeng:0603")
      (description "Resistor")
      (fields (field (name "PUBLISHER") "Altium Limited"))
      (libsource (lib "Miscellaneous Devices") (part "Res1"))
    )
    (comp (ref "R104")
      (value "NULL")
      (footprint "BinFeng:0603")
      (description "Resistor")
      (fields (field (name "PUBLISHER") "Altium Limited"))
      (libsource (lib "Miscellaneous Devices") (part "Res1"))
    )
    (comp (ref "R105")
      (value "NULL")
      (footprint "BinFeng:0603")
      (description "Resistor")
      (fields (field (name "PUBLISHER") "Altium Limited"))
      (libsource (lib "Miscellaneous Devices") (part "Res1"))
    )
    (comp (ref "RS485_2")
      (value "Header 3")
      (footprint "HDR1X3")
      (description "Header, 3-Pin")
      (fields (field (name "PUBLISHER") "Altium Limited"))
      (libsource (lib "Miscellaneous Connectors") (part "Header 3"))
    )
    (comp (ref "SENSE_H")
      (value "SMB")
      (footprint "SMA")
      (description "SMB Straight Connector")
      (fields (field (name "PUBLISHER") "Altium Limited"))
      (libsource (lib "Miscellaneous Connectors") (part "SMB"))
    )
    (comp (ref "SENSE_L")
      (value "SMB")
      (footprint "SMA")
      (description "SMB Straight Connector")
      (fields (field (name "PUBLISHER") "Altium Limited"))
      (libsource (lib "Miscellaneous Connectors") (part "SMB"))
    )
    (comp (ref "T1")
      (value "TestPoint")
      (footprint "TestPoint")
      (libsource (lib "BinFeng_IC") (part "TestPoint"))
    )
    (comp (ref "T2")
      (value "TestPoint")
      (footprint "TestPoint")
      (libsource (lib "BinFeng_IC") (part "TestPoint"))
    )
    (comp (ref "T3")
      (value "TestPoint")
      (footprint "TestPoint")
      (libsource (lib "BinFeng_IC") (part "TestPoint"))
    )
    (comp (ref "T5")
      (value "TestPoint")
      (footprint "TestPoint")
      (libsource (lib "BinFeng_IC") (part "TestPoint"))
    )
    (comp (ref "U1")
      (value "STM32F103RET6")
      (footprint "LQFP64_N")
      (description "STM32 ARM-based 32-bit MCU with 128 Kbytes Flash, 64-pin LQFP, Industrial Temperature")
      (fields (field (name "PUBLISHER") "Altium Limited"))
      (libsource (lib "ST Microcontroller 32-Bit STM32") (part "STM32F103RBT6"))
    )
    (comp (ref "U2") (value "BUF634") (footprint "PSFM-T5") (libsource (lib "BinFeng_IC") (part "BUF634")))
    (comp (ref "U4") (value "AD4522-2") (footprint "SO-8N") (libsource (lib "BinFeng_IC") (part "AD8676")))
    (comp (ref "U6")
      (value "ADA4610-2")
      (footprint "MSO-8")
      (libsource (lib "BinFeng_IC") (part "ADA4610-2"))
    )
    (comp (ref "U7")
      (value "ADA4610-2")
      (footprint "MSO-8")
      (libsource (lib "BinFeng_IC") (part "ADA4610-2"))
    )
    (comp (ref "U8") (value "RT9193") (footprint "SOT-23-5") (libsource (lib "BinFeng_IC") (part "RT9193")))
    (comp (ref "U9") (value "AD8422ARZ") (footprint "SO-8N") (libsource (lib "BinFeng_IC") (part "AD8422")))
    (comp (ref "U10")
      (value "AD7988-1")
      (footprint "MSOP10")
      (libsource (lib "BinFeng_IC") (part "AD7988-1"))
    )
    (comp (ref "U11")
      (value "AD7988-1")
      (footprint "MSOP10")
      (libsource (lib "BinFeng_IC") (part "AD7988-1"))
    )
    (comp (ref "U12")
      (value "ADR441")
      (footprint "SO-8N")
      (description "Ultralow Noise, XFET Voltage References")
      (libsource (lib "BinFeng_IC") (part "ADR441"))
    )
    (comp (ref "U13") (value "AD8676") (footprint "SO-8N") (libsource (lib "BinFeng_IC") (part "AD8676")))
    (comp (ref "U14") (value "AD5689R") (footprint "TSSOP16") (libsource (lib "BinFeng_IC") (part "AD5687R")))
    (comp (ref "U17") (value "AD8253") (footprint "RM-10") (libsource (lib "BinFeng_IC") (part "AD8253")))
    (comp (ref "U18") (value "AD8253") (footprint "RM-10") (libsource (lib "BinFeng_IC") (part "AD8253")))
    (comp (ref "U19") (value "AD8422ARZ") (footprint "SO-8N") (libsource (lib "BinFeng_IC") (part "AD8422")))
    (comp (ref "U23") (value "AD8676") (footprint "SO-8N") (libsource (lib "BinFeng_IC") (part "AD8676")))
    (comp (ref "U44") (value "SP3485") (footprint "SO-8N") (libsource (lib "BinFeng_IC") (part "SP3485")))
    (comp (ref "U45") (value "SP3485") (footprint "SO-8N") (libsource (lib "BinFeng_IC") (part "SP3485")))
    (comp (ref "USB")
      (value "USB")
      (footprint "USB_A")
      (description "USB interface")
      (libsource (lib "BinFeng_Connectors") (part "USB_Normal"))
    )
    (comp (ref "X1") (value "8M smd") (footprint "8Mhz_XTAL") (libsource (lib "Schlib1") (part "8M smd")))
  )
  (nets
    (net (code "1") (name "+15V") (class "Default")
      (node (ref "C100") (pin "1") (pinfunction "1_1") (pintype "passive"))
      (node (ref "C103") (pin "2") (pinfunction "2_2") (pintype "passive"))
      (node (ref "C104") (pin "1") (pinfunction "1_1") (pintype "passive"))
      (node (ref "C110") (pin "2") (pinfunction "2_2") (pintype "passive"))
      (node (ref "C111") (pin "1") (pinfunction "1_1") (pintype "passive"))
      (node (ref "C114") (pin "2") (pinfunction "2_2") (pintype "passive"))
      (node (ref "C115") (pin "1") (pinfunction "1_1") (pintype "passive"))
      (node (ref "C150") (pin "2") (pinfunction "2_2") (pintype "passive"))
      (node (ref "C151") (pin "1") (pinfunction "1_1") (pintype "passive"))
      (node (ref "C19") (pin "2") (pinfunction "2_2") (pintype "passive"))
      (node (ref "C37") (pin "2") (pinfunction "2_2") (pintype "passive"))
      (node (ref "C38") (pin "1") (pinfunction "1_1") (pintype "passive"))
      (node (ref "C39") (pin "2") (pinfunction "2_2") (pintype "passive"))
      (node (ref "C40") (pin "1") (pinfunction "1_1") (pintype "passive"))
      (node (ref "C43") (pin "2") (pinfunction "2_2") (pintype "passive"))
      (node (ref "C44") (pin "1") (pinfunction "1_1") (pintype "passive"))
      (node (ref "K1") (pin "1") (pinfunction "1_1") (pintype "passive"))
      (node (ref "K10") (pin "1") (pinfunction "1_1") (pintype "passive"))
      (node (ref "K11") (pin "2") (pintype "passive"))
      (node (ref "K12") (pin "2") (pintype "passive"))
      (node (ref "K13") (pin "2") (pintype "passive"))
      (node (ref "K14") (pin "2") (pintype "passive"))
      (node (ref "K2") (pin "1") (pinfunction "1_1") (pintype "passive"))
      (node (ref "K3") (pin "1") (pinfunction "1_1") (pintype "passive"))
      (node (ref "K4") (pin "1") (pinfunction "1_1") (pintype "passive"))
      (node (ref "K5") (pin "1") (pinfunction "1_1") (pintype "passive"))
      (node (ref "K6") (pin "1") (pinfunction "1_1") (pintype "passive"))
      (node (ref "K7") (pin "1") (pinfunction "1_1") (pintype "passive"))
      (node (ref "K8") (pin "1") (pinfunction "1_1") (pintype "passive"))
      (node (ref "K9") (pin "1") (pinfunction "1_1") (pintype "passive"))
      (node (ref "U19") (pin "8") (pinfunction "Vs+_8") (pintype "passive"))
      (node (ref "U2") (pin "5") (pinfunction "V+_5") (pintype "passive"))
      (node (ref "U23") (pin "8") (pinfunction "V+_8") (pintype "passive"))
      (node (ref "U4") (pin "8") (pinfunction "V+_8") (pintype "passive"))
      (node (ref "U6") (pin "8") (pinfunction "V+_8") (pintype "passive"))
      (node (ref "U7") (pin "8") (pinfunction "V+_8") (pintype "passive"))
      (node (ref "U9") (pin "8") (pinfunction "Vs+_8") (pintype "passive"))
    )
    (net (code "2") (name "-5V") (class "Default")
      (node (ref "C121") (pin "2") (pinfunction "2_2") (pintype "passive"))
      (node (ref "C14") (pin "2") (pinfunction "2_2") (pintype "passive"))
      (node (ref "C16") (pin "2") (pinfunction "2_2") (pintype "passive"))
      (node (ref "C18") (pin "2") (pinfunction "2_2") (pintype "passive"))
      (node (ref "C95") (pin "2") (pinfunction "2_2") (pintype "passive"))
      (node (ref "U13") (pin "4") (pinfunction "V-_4") (pintype "passive"))
      (node (ref "U17") (pin "3") (pinfunction "-Vs_3") (pintype "passive"))
      (node (ref "U18") (pin "3") (pinfunction "-Vs_3") (pintype "passive"))
    )
    (net (code "3") (name "-15V") (class "Default")
      (node (ref "C101") (pin "2") (pinfunction "2_2") (pintype "passive"))
      (node (ref "C102") (pin "2") (pinfunction "2_2") (pintype "passive"))
      (node (ref "C105") (pin "2") (pinfunction "2_2") (pintype "passive"))
      (node (ref "C106") (pin "2") (pinfunction "2_2") (pintype "passive"))
      (node (ref "C112") (pin "2") (pinfunction "2_2") (pintype "passive"))
      (node (ref "C113") (pin "2") (pinfunction "2_2") (pintype "passive"))
      (node (ref "C116") (pin "2") (pinfunction "2_2") (pintype "passive"))
      (node (ref "C117") (pin "2") (pinfunction "2_2") (pintype "passive"))
      (node (ref "C152") (pin "2") (pinfunction "2_2") (pintype "passive"))
      (node (ref "C153") (pin "2") (pinfunction "2_2") (pintype "passive"))
      (node (ref "C41") (pin "2") (pinfunction "2_2") (pintype "passive"))
      (node (ref "C42") (pin "2") (pinfunction "2_2") (pintype "passive"))
      (node (ref "C45") (pin "2") (pinfunction "2_2") (pintype "passive"))
      (node (ref "C46") (pin "2") (pinfunction "2_2") (pintype "passive"))
      (node (ref "R27") (pin "1") (pinfunction "1_1") (pintype "passive"))
      (node (ref "U19") (pin "5") (pinfunction "Vs-_5") (pintype "passive"))
      (node (ref "U2") (pin "3") (pinfunction "V-_3") (pintype "passive"))
      (node (ref "U23") (pin "4") (pinfunction "V-_4") (pintype "passive"))
      (node (ref "U4") (pin "4") (pinfunction "V-_4") (pintype "passive"))
      (node (ref "U6") (pin "4") (pinfunction "V-_4") (pintype "passive"))
      (node (ref "U7") (pin "4") (pinfunction "V-_4") (pintype "passive"))
      (node (ref "U9") (pin "5") (pinfunction "Vs-_5") (pintype "passive"))
    )
    (net (code "4") (name "/1.25V") (class "Default")
      (node (ref "U13") (pin "6") (pinfunction "-IN_B_6") (pintype "passive"))
      (node (ref "U13") (pin "7") (pinfunction "Out_B_7") (pintype "passive"))
      (node (ref "U17") (pin "9") (pinfunction "REF_9") (pintype "passive"))
      (node (ref "U18") (pin "9") (pinfunction "REF_9") (pintype "passive"))
    )
    (net (code "5") (name "/2.5V") (class "Default")
      (node (ref "C82") (pin "1") (pinfunction "1_1") (pintype "passive"))
      (node (ref "C83") (pin "1") (pinfunction "1_1") (pintype "passive"))
      (node (ref "R22") (pin "1") (pinfunction "1_1") (pintype "passive"))
      (node (ref "R61") (pin "1") (pinfunction "1_1") (pintype "passive"))
      (node (ref "U10") (pin "1") (pinfunction "REF_1") (pintype "passive"))
      (node (ref "U10") (pin "2") (pinfunction "VDD_2") (pintype "passive"))
      (node (ref "U11") (pin "1") (pinfunction "REF_1") (pintype "passive"))
      (node (ref "U11") (pin "2") (pinfunction "VDD_2") (pintype "passive"))
      (node (ref "U13") (pin "1") (pinfunction "Out_A_1") (pintype "passive"))
      (node (ref "U13") (pin "2") (pinfunction "-IN_A_2") (pintype "passive"))
    )
    (net (code "6") (name "/ADC1_CNV") (class "Default")
      (node (ref "U1") (pin "38") (pinfunction "PC7_38") (pintype "bidirectional"))
      (node (ref "U10") (pin "6") (pinfunction "CNV_6") (pintype "passive"))
    )
    (net (code "7") (name "/ADC1_SCK") (class "Default")
      (node (ref "U1") (pin "36") (pinfunction "PB15_36") (pintype "bidirectional"))
      (node (ref "U10") (pin "8") (pinfunction "SCK_8") (pintype "passive"))
    )
    (net (code "8") (name "/ADC1_SDI") (class "Default")
      (node (ref "U1") (pin "35") (pinfunction "PB14_35") (pintype "bidirectional"))
      (node (ref "U10") (pin "9") (pinfunction "SDI_9") (pintype "passive"))
    )
    (net (code "9") (name "/ADC1_SDO") (class "Default")
      (node (ref "U1") (pin "37") (pinfunction "PC6_37") (pintype "bidirectional"))
      (node (ref "U10") (pin "7") (pinfunction "SDO_7") (pintype "passive"))
    )
    (net (code "10") (name "/ADC2_CNV") (class "Default")
      (node (ref "U1") (pin "23") (pinfunction "PA7_23") (pintype "bidirectional"))
      (node (ref "U11") (pin "6") (pinfunction "CNV_6") (pintype "passive"))
    )
    (net (code "11") (name "/ADC2_SCK") (class "Default")
      (node (ref "U1") (pin "21") (pinfunction "PA5_21") (pintype "bidirectional"))
      (node (ref "U11") (pin "8") (pinfunction "SCK_8") (pintype "passive"))
    )
    (net (code "12") (name "/ADC2_SDI") (class "Default")
      (node (ref "U1") (pin "20") (pinfunction "PA4_20") (pintype "bidirectional"))
      (node (ref "U11") (pin "9") (pinfunction "SDI_9") (pintype "passive"))
    )
    (net (code "13") (name "/ADC2_SDO") (class "Default")
      (node (ref "U1") (pin "22") (pinfunction "PA6_22") (pintype "bidirectional"))
      (node (ref "U11") (pin "7") (pinfunction "SDO_7") (pintype "passive"))
    )
    (net (code "14") (name "/Ctrl1") (class "Default")
      (node (ref "Q1") (pin "1") (pinfunction "Gate_1") (pintype "passive"))
      (node (ref "U1") (pin "8") (pinfunction "PC0_8") (pintype "bidirectional"))
    )
    (net (code "15") (name "/Ctrl2") (class "Default")
      (node (ref "Q2") (pin "1") (pinfunction "Gate_1") (pintype "passive"))
      (node (ref "U1") (pin "9") (pinfunction "PC1_9") (pintype "bidirectional"))
    )
    (net (code "16") (name "/Ctrl3") (class "Default")
      (node (ref "Q3") (pin "1") (pinfunction "Gate_1") (pintype "passive"))
      (node (ref "U1") (pin "10") (pinfunction "PC2_10") (pintype "bidirectional"))
    )
    (net (code "17") (name "/Ctrl4") (class "Default")
      (node (ref "Q4") (pin "1") (pinfunction "Gate_1") (pintype "passive"))
      (node (ref "U1") (pin "11") (pinfunction "PC3_11") (pintype "bidirectional"))
    )
    (net (code "18") (name "/Ctrl5") (class "Default")
      (node (ref "Q5") (pin "1") (pinfunction "Gate_1") (pintype "passive"))
      (node (ref "U1") (pin "24") (pinfunction "PC4_24") (pintype "bidirectional"))
    )
    (net (code "19") (name "/Ctrl6") (class "Default")
      (node (ref "Q6") (pin "1") (pinfunction "Gate_1") (pintype "passive"))
      (node (ref "U1") (pin "25") (pinfunction "PC5_25") (pintype "bidirectional"))
    )
    (net (code "20") (name "/Ctrl7") (class "Default")
      (node (ref "Q7") (pin "1") (pinfunction "Gate_1") (pintype "passive"))
      (node (ref "U1") (pin "26") (pinfunction "PB0_26") (pintype "bidirectional"))
    )
    (net (code "21") (name "/Ctrl8") (class "Default")
      (node (ref "Q8") (pin "1") (pinfunction "Gate_1") (pintype "passive"))
      (node (ref "U1") (pin "27") (pinfunction "PB1_27") (pintype "bidirectional"))
    )
    (net (code "22") (name "/Ctrl9") (class "Default")
      (node (ref "Q9") (pin "1") (pinfunction "Gate_1") (pintype "passive"))
      (node (ref "U1") (pin "28") (pinfunction "PB2/BOOT1_28") (pintype "bidirectional"))
    )
    (net (code "23") (name "/Ctrl10") (class "Default")
      (node (ref "Q10") (pin "1") (pinfunction "Gate_1") (pintype "passive"))
      (node (ref "U1") (pin "33") (pinfunction "PB12_33") (pintype "bidirectional"))
    )
    (net (code "24") (name "/Ctrl11") (class "Default")
      (node (ref "Q11") (pin "1") (pinfunction "Gate_1") (pintype "passive"))
      (node (ref "U1") (pin "55") (pinfunction "PB3/JTDO_55") (pintype "bidirectional"))
    )
    (net (code "25") (name "/Ctrl12") (class "Default")
      (node (ref "Q12") (pin "1") (pinfunction "Gate_1") (pintype "passive"))
      (node (ref "U1") (pin "34") (pinfunction "PB13_34") (pintype "bidirectional"))
    )
    (net (code "26") (name "/Ctrl13") (class "Default")
      (node (ref "Q13") (pin "1") (pinfunction "Gate_1") (pintype "passive"))
      (node (ref "U1") (pin "56") (pinfunction "PB4/JNTRST_56") (pintype "bidirectional"))
    )
    (net (code "27") (name "/Ctrl14") (class "Default")
      (node (ref "Q14") (pin "1") (pinfunction "Gate_1") (pintype "passive"))
      (node (ref "U1") (pin "57") (pinfunction "PB5_57") (pintype "bidirectional"))
    )
    (net (code "28") (name "/Ctrl17") (class "Default")
      (node (ref "U1") (pin "62") (pinfunction "PB9_62") (pintype "bidirectional"))
    )
    (net (code "29") (name "/D1") (class "Default")
      (node (ref "K1") (pin "8") (pinfunction "8_8") (pintype "passive"))
      (node (ref "Q1") (pin "3") (pinfunction "Drain_3") (pintype "passive"))
    )
    (net (code "30") (name "/D2") (class "Default")
      (node (ref "K2") (pin "8") (pinfunction "8_8") (pintype "passive"))
      (node (ref "Q2") (pin "3") (pinfunction "Drain_3") (pintype "passive"))
    )
    (net (code "31") (name "/D3") (class "Default")
      (node (ref "K3") (pin "8") (pinfunction "8_8") (pintype "passive"))
      (node (ref "Q3") (pin "3") (pinfunction "Drain_3") (pintype "passive"))
    )
    (net (code "32") (name "/D4") (class "Default")
      (node (ref "K4") (pin "8") (pinfunction "8_8") (pintype "passive"))
      (node (ref "Q4") (pin "3") (pinfunction "Drain_3") (pintype "passive"))
    )
    (net (code "33") (name "/D5") (class "Default")
      (node (ref "K5") (pin "8") (pinfunction "8_8") (pintype "passive"))
      (node (ref "Q5") (pin "3") (pinfunction "Drain_3") (pintype "passive"))
    )
    (net (code "34") (name "/D6") (class "Default")
      (node (ref "K6") (pin "8") (pinfunction "8_8") (pintype "passive"))
      (node (ref "Q6") (pin "3") (pinfunction "Drain_3") (pintype "passive"))
    )
    (net (code "35") (name "/D7") (class "Default")
      (node (ref "K7") (pin "8") (pinfunction "8_8") (pintype "passive"))
      (node (ref "Q7") (pin "3") (pinfunction "Drain_3") (pintype "passive"))
    )
    (net (code "36") (name "/D8") (class "Default")
      (node (ref "K8") (pin "8") (pinfunction "8_8") (pintype "passive"))
      (node (ref "Q8") (pin "3") (pinfunction "Drain_3") (pintype "passive"))
    )
    (net (code "37") (name "/D9") (class "Default")
      (node (ref "K9") (pin "8") (pinfunction "8_8") (pintype "passive"))
      (node (ref "Q9") (pin "3") (pinfunction "Drain_3") (pintype "passive"))
    )
    (net (code "38") (name "/D10") (class "Default")
      (node (ref "K10") (pin "8") (pinfunction "8_8") (pintype "passive"))
      (node (ref "Q10") (pin "3") (pinfunction "Drain_3") (pintype "passive"))
    )
    (net (code "39") (name "/D11") (class "Default")
      (node (ref "K11") (pin "5") (pintype "passive"))
      (node (ref "Q11") (pin "3") (pinfunction "Drain_3") (pintype "passive"))
    )
    (net (code "40") (name "/D12") (class "Default")
      (node (ref "K12") (pin "5") (pintype "passive"))
      (node (ref "Q12") (pin "3") (pinfunction "Drain_3") (pintype "passive"))
    )
    (net (code "41") (name "/D13") (class "Default")
      (node (ref "K13") (pin "5") (pintype "passive"))
      (node (ref "Q13") (pin "3") (pinfunction "Drain_3") (pintype "passive"))
    )
    (net (code "42") (name "/D14") (class "Default")
      (node (ref "K14") (pin "5") (pintype "passive"))
      (node (ref "Q14") (pin "3") (pinfunction "Drain_3") (pintype "passive"))
    )
    (net (code "43") (name "/DAC1_FSYNC") (class "Default")
      (node (ref "U1") (pin "41") (pinfunction "PA8_41") (pintype "bidirectional"))
      (node (ref "U14") (pin "13") (pinfunction "/SYNC_13") (pintype "passive"))
    )
    (net (code "44") (name "/DAC1_RESET") (class "Default")
      (node (ref "U1") (pin "14") (pinfunction "PA0-WKUP_14") (pintype "bidirectional"))
      (node (ref "U14") (pin "15") (pinfunction "/RESET_15") (pintype "passive"))
    )
    (net (code "45") (name "/DAC1_SCLK") (class "Default")
      (node (ref "U1") (pin "40") (pinfunction "PC9_40") (pintype "bidirectional"))
      (node (ref "U14") (pin "12") (pinfunction "SCLK_12") (pintype "passive"))
    )
    (net (code "46") (name "/DAC1_SDATA") (class "Default")
      (node (ref "U1") (pin "15") (pinfunction "PA1_15") (pintype "bidirectional"))
      (node (ref "U14") (pin "14") (pinfunction "SDIN_14") (pintype "passive"))
    )
    (net (code "47") (name "/DUT_VOLTAGE") (class "Default")
      (node (ref "R51") (pin "2") (pinfunction "2_2") (pintype "passive"))
      (node (ref "T2") (pin "1") (pinfunction "1_1") (pintype "passive"))
      (node (ref "U19") (pin "7") (pinfunction "Vout_7") (pintype "passive"))
    )
    (net (code "48") (name "/DUT_VOL_DIV") (class "Default")
      (node (ref "K13") (pin "1") (pintype "passive"))
      (node (ref "R51") (pin "1") (pinfunction "1_1") (pintype "passive"))
      (node (ref "R52") (pin "2") (pinfunction "2_2") (pintype "passive"))
      (node (ref "U18") (pin "10") (pinfunction "+IN_10") (pintype "passive"))
    )
    (net (code "49") (name "/DUT_VOL_H") (class "Default")
      (node (ref "R56") (pin "1") (pinfunction "1_1") (pintype "passive"))
      (node (ref "U7") (pin "6") (pinfunction "-IN_B_6") (pintype "passive"))
      (node (ref "U7") (pin "7") (pinfunction "OUT_B_7") (pintype "passive"))
    )
    (net (code "50") (name "/DUT_VOL_L") (class "Default")
      (node (ref "R55") (pin "1") (pinfunction "1_1") (pintype "passive"))
      (node (ref "U7") (pin "1") (pinfunction "OUT_A_1") (pintype "passive"))
      (node (ref "U7") (pin "2") (pinfunction "-IN_A_2") (pintype "passive"))
    )
    (net (code "51") (name "/FB_R_T1") (class "Default")
      (node (ref "C70") (pin "1") (pinfunction "1_1") (pintype "passive"))
      (node (ref "C71") (pin "1") (pinfunction "1_1") (pintype "passive"))
      (node (ref "C72") (pin "1") (pinfunction "1_1") (pintype "passive"))
      (node (ref "C73") (pin "1") (pinfunction "1_1") (pintype "passive"))
      (node (ref "C74") (pin "1") (pinfunction "1_1") (pintype "passive"))
      (node (ref "C75") (pin "1") (pinfunction "1_1") (pintype "passive"))
      (node (ref "C76") (pin "1") (pinfunction "1_1") (pintype "passive"))
      (node (ref "C77") (pin "1") (pinfunction "1_1") (pintype "passive"))
      (node (ref "C78") (pin "1") (pinfunction "1_1") (pintype "passive"))
      (node (ref "C79") (pin "1") (pinfunction "1_1") (pintype "passive"))
      (node (ref "K14") (pin "6") (pintype "passive"))
      (node (ref "R31") (pin "1") (pinfunction "1_1") (pintype "passive"))
      (node (ref "R32") (pin "1") (pinfunction "1_1") (pintype "passive"))
      (node (ref "R33") (pin "1") (pinfunction "1_1") (pintype "passive"))
      (node (ref "R34") (pin "1") (pinfunction "1_1") (pintype "passive"))
      (node (ref "R35") (pin "1") (pinfunction "1_1") (pintype "passive"))
      (node (ref "R36") (pin "1") (pinfunction "1_1") (pintype "passive"))
      (node (ref "R37") (pin "1") (pinfunction "1_1") (pintype "passive"))
      (node (ref "R38") (pin "1") (pinfunction "1_1") (pintype "passive"))
      (node (ref "R39") (pin "1") (pinfunction "1_1") (pintype "passive"))
      (node (ref "R40") (pin "1") (pinfunction "1_1") (pintype "passive"))
    )
    (net (code "52") (name "/FB_R_T2") (class "Default")
      (node (ref "K1") (pin "5") (pinfunction "5_5") (pintype "passive"))
      (node (ref "K10") (pin "5") (pinfunction "5_5") (pintype "passive"))
      (node (ref "K2") (pin "5") (pinfunction "5_5") (pintype "passive"))
      (node (ref "K3") (pin "5") (pinfunction "5_5") (pintype "passive"))
      (node (ref "K4") (pin "5") (pinfunction "5_5") (pintype "passive"))
      (node (ref "K5") (pin "5") (pinfunction "5_5") (pintype "passive"))
      (node (ref "K6") (pin "5") (pinfunction "5_5") (pintype "passive"))
      (node (ref "K7") (pin "5") (pinfunction "5_5") (pintype "passive"))
      (node (ref "K8") (pin "5") (pinfunction "5_5") (pintype "passive"))
      (node (ref "K9") (pin "5") (pinfunction "5_5") (pintype "passive"))
      (node (ref "R21") (pin "2") (pinfunction "2_2") (pintype "passive"))
      (node (ref "U2") (pin "4") (pinfunction "Vout_4") (pintype "passive"))
    )
    (net (code "53") (name "/FH_Out") (class "Default")
      (node (ref "FORCE_H") (pin "1") (pinfunction "X_1") (pintype "passive"))
      (node (ref "K14") (pin "4") (pintype "passive"))
      (node (ref "R19") (pin "2") (pinfunction "2_2") (pintype "passive"))
      (node (ref "R76") (pin "1") (pinfunction "1_1") (pintype "passive"))
      (node (ref "U4") (pin "5") (pinfunction "+IN_B_5") (pintype "passive"))
    )
    (net (code "54") (name "/LED0") (class "Default")
      (node (ref "R68") (pin "2") (pinfunction "2_2") (pintype "passive"))
      (node (ref "U1") (pin "53") (pinfunction "PC12_53") (pintype "bidirectional"))
    )
    (net (code "55") (name "/LED1") (class "Default")
      (node (ref "R69") (pin "2") (pinfunction "2_2") (pintype "passive"))
      (node (ref "U1") (pin "54") (pinfunction "PD2_54") (pintype "bidirectional"))
    )
    (net (code "56") (name "/NULL") (class "Default")
      (node (ref "C47") (pin "1") (pinfunction "1_1") (pintype "passive"))
      (node (ref "U14") (pin "7") (pinfunction "VoutB_7") (pintype "passive"))
    )
    (net (code "57") (name "/PGA1_A0") (class "Default")
      (node (ref "U1") (pin "61") (pinfunction "PB8_61") (pintype "bidirectional"))
      (node (ref "U17") (pin "4") (pinfunction "A0_4") (pintype "passive"))
    )
    (net (code "58") (name "/PGA1_A1") (class "Default")
      (node (ref "U1") (pin "51") (pinfunction "PC10_51") (pintype "bidirectional"))
      (node (ref "U17") (pin "5") (pinfunction "A1_5") (pintype "passive"))
    )
    (net (code "59") (name "/PGA1_WR") (class "Default")
      (node (ref "U1") (pin "59") (pinfunction "PB7_59") (pintype "bidirectional"))
      (node (ref "U17") (pin "6") (pinfunction "/WR_6") (pintype "passive"))
    )
    (net (code "60") (name "/PGA2_A0") (class "Default")
      (node (ref "U1") (pin "50") (pinfunction "PA15/JTDI_50") (pintype "bidirectional"))
      (node (ref "U18") (pin "4") (pinfunction "A0_4") (pintype "passive"))
    )
    (net (code "61") (name "/PGA2_A1") (class "Default")
      (node (ref "U1") (pin "52") (pinfunction "PC11_52") (pintype "bidirectional"))
      (node (ref "U18") (pin "5") (pinfunction "A1_5") (pintype "passive"))
    )
    (net (code "62") (name "/PGA2_WR") (class "Default")
      (node (ref "U1") (pin "2") (pinfunction "PC13-TAMPER-RTC_2") (pintype "bidirectional"))
      (node (ref "U18") (pin "6") (pinfunction "/WR_6") (pintype "passive"))
    )
    (net (code "63") (name "/RS485_RE") (class "Default")
      (node (ref "U1") (pin "58") (pinfunction "PB6_58") (pintype "bidirectional"))
      (node (ref "U44") (pin "2") (pinfunction "/RE_2") (pintype "passive"))
      (node (ref "U44") (pin "3") (pinfunction "DE_3") (pintype "passive"))
    )
    (net (code "64") (name "/RS485_RE2") (class "Default")
      (node (ref "U1") (pin "39") (pinfunction "PC8_39") (pintype "bidirectional"))
      (node (ref "U45") (pin "2") (pinfunction "/RE_2") (pintype "passive"))
      (node (ref "U45") (pin "3") (pinfunction "DE_3") (pintype "passive"))
    )
    (net (code "65") (name "/R_VOLTAGE") (class "Default")
      (node (ref "R49") (pin "2") (pinfunction "2_2") (pintype "passive"))
      (node (ref "T1") (pin "1") (pinfunction "1_1") (pintype "passive"))
      (node (ref "U9") (pin "7") (pinfunction "Vout_7") (pintype "passive"))
    )
    (net (code "66") (name "/R_VOL_DIV") (class "Default")
      (node (ref "K13") (pin "6") (pintype "passive"))
      (node (ref "R49") (pin "1") (pinfunction "1_1") (pintype "passive"))
      (node (ref "R50") (pin "2") (pinfunction "2_2") (pintype "passive"))
      (node (ref "U17") (pin "10") (pinfunction "+IN_10") (pintype "passive"))
    )
    (net (code "67") (name "/R_VOL_H") (class "Default")
      (node (ref "R54") (pin "2") (pinfunction "2_2") (pintype "passive"))
      (node (ref "U6") (pin "1") (pinfunction "OUT_A_1") (pintype "passive"))
      (node (ref "U6") (pin "2") (pinfunction "-IN_A_2") (pintype "passive"))
    )
    (net (code "68") (name "/R_VOL_L") (class "Default")
      (node (ref "R53") (pin "2") (pinfunction "2_2") (pintype "passive"))
      (node (ref "U6") (pin "6") (pinfunction "-IN_B_6") (pintype "passive"))
      (node (ref "U6") (pin "7") (pinfunction "OUT_B_7") (pintype "passive"))
    )
    (net (code "69") (name "/SENSE_H") (class "Default")
      (node (ref "R14") (pin "1") (pinfunction "1_1") (pintype "passive"))
      (node (ref "R76") (pin "2") (pinfunction "2_2") (pintype "passive"))
      (node (ref "SENSE_H") (pin "1") (pinfunction "X_1") (pintype "passive"))
    )
    (net (code "70") (name "/SENSE_L") (class "Default")
      (node (ref "R12") (pin "1") (pinfunction "1_1") (pintype "passive"))
      (node (ref "R75") (pin "1") (pinfunction "1_1") (pintype "passive"))
      (node (ref "SENSE_L") (pin "1") (pinfunction "X_1") (pintype "passive"))
    )
    (net (code "71") (name "/SWCLK") (class "Default")
      (node (ref "DL") (pin "2") (pinfunction "D-_2") (pintype "passive"))
      (node (ref "U1") (pin "49") (pinfunction "PA14/JTCK/SWCLK_49") (pintype "bidirectional"))
    )
    (net (code "72") (name "/SWDIO") (class "Default")
      (node (ref "DL") (pin "3") (pinfunction "D+_3") (pintype "passive"))
      (node (ref "DL") (pin "4") (pinfunction "ID_4") (pintype "passive"))
      (node (ref "U1") (pin "46") (pinfunction "PA13/JTMS/SWDIO_46") (pintype "bidirectional"))
    )
    (net (code "73") (name "/SigIn") (class "Default")
      (node (ref "C154") (pin "2") (pinfunction "2_2") (pintype "passive"))
      (node (ref "R17") (pin "2") (pinfunction "2_2") (pintype "passive"))
      (node (ref "R25") (pin "2") (pinfunction "2_2") (pintype "passive"))
      (node (ref "T3") (pin "1") (pinfunction "1_1") (pintype "passive"))
      (node (ref "U23") (pin "1") (pinfunction "Out_A_1") (pintype "passive"))
    )
    (net (code "74") (name "/SigOut") (class "Default")
      (node (ref "C48") (pin "1") (pinfunction "1_1") (pintype "passive"))
      (node (ref "R24") (pin "1") (pinfunction "1_1") (pintype "passive"))
      (node (ref "U14") (pin "3") (pinfunction "VoutA_3") (pintype "passive"))
    )
    (net (code "75") (name "/UART3_RX") (class "Default")
      (node (ref "LCD") (pin "5") (pinfunction "5_5") (pintype "passive"))
      (node (ref "U1") (pin "30") (pinfunction "PB11_30") (pintype "bidirectional"))
    )
    (net (code "76") (name "/UART3_TX") (class "Default")
      (node (ref "LCD") (pin "3") (pinfunction "3_3") (pintype "passive"))
      (node (ref "LCD") (pin "4") (pinfunction "4_4") (pintype "passive"))
      (node (ref "U1") (pin "29") (pinfunction "PB10_29") (pintype "bidirectional"))
    )
    (net (code "77") (name "/USART1_RX") (class "Default")
      (node (ref "U1") (pin "43") (pinfunction "PA10_43") (pintype "bidirectional"))
      (node (ref "U44") (pin "1") (pinfunction "RO_1") (pintype "passive"))
    )
    (net (code "78") (name "/USART1_TX") (class "Default")
      (node (ref "U1") (pin "42") (pinfunction "PA9_42") (pintype "bidirectional"))
      (node (ref "U44") (pin "4") (pinfunction "DI_4") (pintype "passive"))
    )
    (net (code "79") (name "/USART2_RX") (class "Default")
      (node (ref "U1") (pin "17") (pinfunction "PA3_17") (pintype "bidirectional"))
      (node (ref "U45") (pin "1") (pinfunction "RO_1") (pintype "passive"))
    )
    (net (code "80") (name "/USART2_TX") (class "Default")
      (node (ref "U1") (pin "16") (pinfunction "PA2_16") (pintype "bidirectional"))
      (node (ref "U45") (pin "4") (pinfunction "DI_4") (pintype "passive"))
    )
    (net (code "81") (name "/USB_DM") (class "Default")
      (node (ref "R43") (pin "2") (pinfunction "2_2") (pintype "passive"))
      (node (ref "U1") (pin "44") (pinfunction "PA11_44") (pintype "bidirectional"))
    )
    (net (code "82") (name "/USB_DP") (class "Default")
      (node (ref "R41") (pin "2") (pinfunction "2_2") (pintype "passive"))
      (node (ref "R42") (pin "2") (pinfunction "2_2") (pintype "passive"))
      (node (ref "U1") (pin "45") (pinfunction "PA12_45") (pintype "bidirectional"))
    )
    (net (code "83") (name "5V") (class "Default")
      (node (ref "C10") (pin "1") (pinfunction "1_1") (pintype "passive"))
      (node (ref "C120") (pin "2") (pinfunction "2_2") (pintype "passive"))
      (node (ref "C13") (pin "2") (pinfunction "2_2") (pintype "passive"))
      (node (ref "C15") (pin "1") (pinfunction "1_1") (pintype "passive"))
      (node (ref "C156") (pin "1") (pinfunction "1_1") (pintype "passive"))
      (node (ref "C17") (pin "1") (pinfunction "1_1") (pintype "passive"))
      (node (ref "C9") (pin "2") (pinfunction "2_2") (pintype "passive"))
      (node (ref "C93") (pin "1") (pinfunction "1_1") (pintype "passive"))
      (node (ref "C94") (pin "2") (pinfunction "2_2") (pintype "passive"))
      (node (ref "U12") (pin "2") (pinfunction "Vin_2") (pintype "passive"))
      (node (ref "U13") (pin "8") (pinfunction "V+_8") (pintype "passive"))
      (node (ref "U14") (pin "5") (pinfunction "Vdd_5") (pintype "passive"))
      (node (ref "U17") (pin "8") (pinfunction "+Vs_8") (pintype "passive"))
      (node (ref "U18") (pin "8") (pinfunction "+Vs_8") (pintype "passive"))
    )
    (net (code "84") (name "AGND") (class "Default")
      (node (ref "C10") (pin "2") (pinfunction "2_2") (pintype "passive"))
      (node (ref "C100") (pin "2") (pinfunction "2_2") (pintype "passive"))
      (node (ref "C101") (pin "1") (pinfunction "1_1") (pintype "passive"))
      (node (ref "C102") (pin "1") (pinfunction "1_1") (pintype "passive"))
      (node (ref "C103") (pin "1") (pinfunction "1_1") (pintype "passive"))
      (node (ref "C104") (pin "2") (pinfunction "2_2") (pintype "passive"))
      (node (ref "C105") (pin "1") (pinfunction "1_1") (pintype "passive"))
      (node (ref "C106") (pin "1") (pinfunction "1_1") (pintype "passive"))
      (node (ref "C110") (pin "1") (pinfunction "1_1") (pintype "passive"))
      (node (ref "C111") (pin "2") (pinfunction "2_2") (pintype "passive"))
      (node (ref "C112") (pin "1") (pinfunction "1_1") (pintype "passive"))
      (node (ref "C113") (pin "1") (pinfunction "1_1") (pintype "passive"))
      (node (ref "C114") (pin "1") (pinfunction "1_1") (pintype "passive"))
      (node (ref "C115") (pin "2") (pinfunction "2_2") (pintype "passive"))
      (node (ref "C116") (pin "1") (pinfunction "1_1") (pintype "passive"))
      (node (ref "C117") (pin "1") (pinfunction "1_1") (pintype "passive"))
      (node (ref "C120") (pin "1") (pinfunction "1_1") (pintype "passive"))
      (node (ref "C121") (pin "1") (pinfunction "1_1") (pintype "passive"))
      (node (ref "C13") (pin "1") (pinfunction "1_1") (pintype "passive"))
      (node (ref "C14") (pin "1") (pinfunction "1_1") (pintype "passive"))
      (node (ref "C15") (pin "2") (pinfunction "2_2") (pintype "passive"))
      (node (ref "C150") (pin "1") (pinfunction "1_1") (pintype "passive"))
      (node (ref "C151") (pin "2") (pinfunction "2_2") (pintype "passive"))
      (node (ref "C152") (pin "1") (pinfunction "1_1") (pintype "passive"))
      (node (ref "C153") (pin "1") (pinfunction "1_1") (pintype "passive"))
      (node (ref "C156") (pin "2") (pinfunction "2_2") (pintype "passive"))
      (node (ref "C16") (pin "1") (pinfunction "1_1") (pintype "passive"))
      (node (ref "C17") (pin "2") (pinfunction "2_2") (pintype "passive"))
      (node (ref "C18") (pin "1") (pinfunction "1_1") (pintype "passive"))
      (node (ref "C19") (pin "1") (pinfunction "1_1") (pintype "passive"))
      (node (ref "C21") (pin "2") (pinfunction "2_2") (pintype "passive"))
      (node (ref "C31") (pin "1") (pinfunction "1_1") (pintype "passive"))
      (node (ref "C32") (pin "2") (pinfunction "2_2") (pintype "passive"))
      (node (ref "C33") (pin "1") (pinfunction "1_1") (pintype "passive"))
      (node (ref "C35") (pin "2") (pinfunction "2_2") (pintype "passive"))
      (node (ref "C37") (pin "1") (pinfunction "1_1") (pintype "passive"))
      (node (ref "C38") (pin "2") (pinfunction "2_2") (pintype "passive"))
      (node (ref "C39") (pin "1") (pinfunction "1_1") (pintype "passive"))
      (node (ref "C40") (pin "2") (pinfunction "2_2") (pintype "passive"))
      (node (ref "C41") (pin "1") (pinfunction "1_1") (pintype "passive"))
      (node (ref "C42") (pin "1") (pinfunction "1_1") (pintype "passive"))
      (node (ref "C43") (pin "1") (pinfunction "1_1") (pintype "passive"))
      (node (ref "C44") (pin "2") (pinfunction "2_2") (pintype "passive"))
      (node (ref "C45") (pin "1") (pinfunction "1_1") (pintype "passive"))
      (node (ref "C46") (pin "1") (pinfunction "1_1") (pintype "passive"))
      (node (ref "C47") (pin "2") (pinfunction "2_2") (pintype "passive"))
      (node (ref "C48") (pin "2") (pinfunction "2_2") (pintype "passive"))
      (node (ref "C49") (pin "2") (pinfunction "2_2") (pintype "passive"))
      (node (ref "C80") (pin "2") (pinfunction "2_2") (pintype "passive"))
      (node (ref "C82") (pin "2") (pinfunction "2_2") (pintype "passive"))
      (node (ref "C83") (pin "2") (pinfunction "2_2") (pintype "passive"))
      (node (ref "C84") (pin "1") (pinfunction "1_1") (pintype "passive"))
      (node (ref "C9") (pin "1") (pinfunction "1_1") (pintype "passive"))
      (node (ref "C90") (pin "1") (pinfunction "1_1") (pintype "passive"))
      (node (ref "C93") (pin "2") (pinfunction "2_2") (pintype "passive"))
      (node (ref "C94") (pin "1") (pinfunction "1_1") (pintype "passive"))
      (node (ref "C95") (pin "1") (pinfunction "1_1") (pintype "passive"))
      (node (ref "DL") (pin "5") (pinfunction "VSS_5") (pintype "passive"))
      (node (ref "FORCE_L") (pin "1") (pinfunction "X_1") (pintype "passive"))
      (node (ref "FORCE_L") (pin "2") (pinfunction "Y_2") (pintype "passive"))
      (node (ref "GUARD") (pin "2") (pinfunction "Y_2") (pintype "passive"))
      (node (ref "K11") (pin "6") (pintype "passive"))
      (node (ref "K12") (pin "6") (pintype "passive"))
      (node (ref "K14") (pin "1") (pintype "passive"))
      (node (ref "L3") (pin "1") (pinfunction "1_1") (pintype "passive"))
      (node (ref "Q1") (pin "2") (pinfunction "Source_2") (pintype "passive"))
      (node (ref "Q10") (pin "2") (pinfunction "Source_2") (pintype "passive"))
      (node (ref "Q11") (pin "2") (pinfunction "Source_2") (pintype "passive"))
      (node (ref "Q12") (pin "2") (pinfunction "Source_2") (pintype "passive"))
      (node (ref "Q13") (pin "2") (pinfunction "Source_2") (pintype "passive"))
      (node (ref "Q14") (pin "2") (pinfunction "Source_2") (pintype "passive"))
      (node (ref "Q2") (pin "2") (pinfunction "Source_2") (pintype "passive"))
      (node (ref "Q3") (pin "2") (pinfunction "Source_2") (pintype "passive"))
      (node (ref "Q4") (pin "2") (pinfunction "Source_2") (pintype "passive"))
      (node (ref "Q5") (pin "2") (pinfunction "Source_2") (pintype "passive"))
      (node (ref "Q6") (pin "2") (pinfunction "Source_2") (pintype "passive"))
      (node (ref "Q7") (pin "2") (pinfunction "Source_2") (pintype "passive"))
      (node (ref "Q8") (pin "2") (pinfunction "Source_2") (pintype "passive"))
      (node (ref "Q9") (pin "2") (pinfunction "Source_2") (pintype "passive"))
      (node (ref "R23") (pin "1") (pinfunction "1_1") (pintype "passive"))
      (node (ref "R62") (pin "2") (pinfunction "2_2") (pintype "passive"))
      (node (ref "R75") (pin "2") (pinfunction "2_2") (pintype "passive"))
      (node (ref "SENSE_L") (pin "2") (pinfunction "Y_2") (pintype "passive"))
      (node (ref "T5") (pin "1") (pinfunction "1_1") (pintype "passive"))
      (node (ref "U10") (pin "4") (pinfunction "IN-_4") (pintype "passive"))
      (node (ref "U10") (pin "5") (pinfunction "GND_5") (pintype "passive"))
      (node (ref "U11") (pin "4") (pinfunction "IN-_4") (pintype "passive"))
      (node (ref "U11") (pin "5") (pinfunction "GND_5") (pintype "passive"))
      (node (ref "U12") (pin "4") (pinfunction "GND_4") (pintype "passive"))
      (node (ref "U14") (pin "16") (pinfunction "RSTSEL_16") (pintype "passive"))
      (node (ref "U14") (pin "4") (pinfunction "GND_4") (pintype "passive"))
      (node (ref "U14") (pin "9") (pinfunction "/LDAC_9") (pintype "passive"))
      (node (ref "U17") (pin "1") (pinfunction "-IN_1") (pintype "passive"))
      (node (ref "U17") (pin "2") (pinfunction "DGND_2") (pintype "passive"))
      (node (ref "U18") (pin "1") (pinfunction "-IN_1") (pintype "passive"))
      (node (ref "U18") (pin "2") (pinfunction "DGND_2") (pintype "passive"))
      (node (ref "U19") (pin "6") (pinfunction "Ref_6") (pintype "passive"))
      (node (ref "U23") (pin "5") (pinfunction "+IN_B_5") (pintype "passive"))
      (node (ref "U9") (pin "6") (pinfunction "Ref_6") (pintype "passive"))
    )
    (net (code "85") (name "D3V3") (class "Default")
      (node (ref "C1") (pin "2") (pinfunction "2_2") (pintype "passive"))
      (node (ref "C108") (pin "2") (pinfunction "2_2") (pintype "passive"))
      (node (ref "C2") (pin "2") (pinfunction "2_2") (pintype "passive"))
      (node (ref "C22") (pin "2") (pinfunction "2_2") (pintype "passive"))
      (node (ref "C29") (pin "2") (pinfunction "2_2") (pintype "passive"))
      (node (ref "C3") (pin "2") (pinfunction "2_2") (pintype "passive"))
      (node (ref "C4") (pin "2") (pinfunction "2_2") (pintype "passive"))
      (node (ref "C5") (pin "2") (pinfunction "2_2") (pintype "passive"))
      (node (ref "C6") (pin "2") (pinfunction "2_2") (pintype "passive"))
      (node (ref "C81") (pin "2") (pinfunction "2_2") (pintype "passive"))
      (node (ref "C85") (pin "2") (pinfunction "2_2") (pintype "passive"))
      (node (ref "LED0") (pin "2") (pinfunction "2_2") (pintype "passive"))
      (node (ref "LED1") (pin "2") (pinfunction "2_2") (pintype "passive"))
      (node (ref "R102") (pin "2") (pinfunction "2_2") (pintype "passive"))
      (node (ref "R105") (pin "2") (pinfunction "2_2") (pintype "passive"))
      (node (ref "R42") (pin "1") (pinfunction "1_1") (pintype "passive"))
      (node (ref "U1") (pin "1") (pinfunction "VBAT_1") (pintype "power_in"))
      (node (ref "U1") (pin "13") (pinfunction "VDDA_13") (pintype "power_in"))
      (node (ref "U1") (pin "19") (pinfunction "VDD_4_19") (pintype "power_in"))
      (node (ref "U1") (pin "32") (pinfunction "VDD_1_32") (pintype "power_in"))
      (node (ref "U1") (pin "48") (pinfunction "VDD_2_48") (pintype "power_in"))
      (node (ref "U1") (pin "64") (pinfunction "VDD_3_64") (pintype "power_in"))
      (node (ref "U10") (pin "10") (pinfunction "VIO_10") (pintype "passive"))
      (node (ref "U11") (pin "10") (pinfunction "VIO_10") (pintype "passive"))
      (node (ref "U14") (pin "10") (pinfunction "GAIN_10") (pintype "passive"))
      (node (ref "U14") (pin "11") (pinfunction "Vlogic_11") (pintype "passive"))
      (node (ref "U44") (pin "8") (pinfunction "VCC_8") (pintype "passive"))
      (node (ref "U45") (pin "8") (pinfunction "VCC_8") (pintype "passive"))
      (node (ref "U8") (pin "5") (pinfunction "VOUT_5") (pintype "passive"))
    )
    (net (code "86") (name "D5V0") (class "Default")
      (node (ref "C57") (pin "2") (pinfunction "2_2") (pintype "passive"))
      (node (ref "C58") (pin "2") (pinfunction "2_2") (pintype "passive"))
      (node (ref "C59") (pin "1") (pinfunction "1_1") (pintype "passive"))
      (node (ref "LCD") (pin "7") (pinfunction "7_7") (pintype "passive"))
      (node (ref "LCD") (pin "8") (pinfunction "8_8") (pintype "passive"))
      (node (ref "U8") (pin "1") (pinfunction "VIN_1") (pintype "passive"))
      (node (ref "U8") (pin "3") (pinfunction "EN_3") (pintype "passive"))
    )
    (net (code "87") (name "DGND") (class "Default")
      (node (ref "C1") (pin "1") (pinfunction "1_1") (pintype "passive"))
      (node (ref "C108") (pin "1") (pinfunction "1_1") (pintype "passive"))
      (node (ref "C2") (pin "1") (pinfunction "1_1") (pintype "passive"))
      (node (ref "C22") (pin "1") (pinfunction "1_1") (pintype "passive"))
      (node (ref "C23") (pin "1") (pinfunction "1_1") (pintype "passive"))
      (node (ref "C29") (pin "1") (pinfunction "1_1") (pintype "passive"))
      (node (ref "C3") (pin "1") (pinfunction "1_1") (pintype "passive"))
      (node (ref "C4") (pin "1") (pinfunction "1_1") (pintype "passive"))
      (node (ref "C5") (pin "1") (pinfunction "1_1") (pintype "passive"))
      (node (ref "C57") (pin "1") (pinfunction "1_1") (pintype "passive"))
      (node (ref "C58") (pin "1") (pinfunction "1_1") (pintype "passive"))
      (node (ref "C59") (pin "2") (pinfunction "2_2") (pintype "passive"))
      (node (ref "C6") (pin "1") (pinfunction "1_1") (pintype "passive"))
      (node (ref "C81") (pin "1") (pinfunction "1_1") (pintype "passive"))
      (node (ref "C85") (pin "1") (pinfunction "1_1") (pintype "passive"))
      (node (ref "L1") (pin "2") (pinfunction "2_2") (pintype "passive"))
      (node (ref "L3") (pin "2") (pinfunction "2_2") (pintype "passive"))
      (node (ref "LCD") (pin "1") (pinfunction "1_1") (pintype "passive"))
      (node (ref "LCD") (pin "2") (pinfunction "2_2") (pintype "passive"))
      (node (ref "R101") (pin "2") (pinfunction "2_2") (pintype "passive"))
      (node (ref "R104") (pin "2") (pinfunction "2_2") (pintype "passive"))
      (node (ref "R2") (pin "2") (pinfunction "2_2") (pintype "passive"))
      (node (ref "R66") (pin "1") (pinfunction "1_1") (pintype "passive"))
      (node (ref "RS485_2") (pin "3") (pinfunction "3_3") (pintype "passive"))
      (node (ref "U1") (pin "12") (pinfunction "VSSA_12") (pintype "power_in"))
      (node (ref "U1") (pin "18") (pinfunction "VSS_4_18") (pintype "power_in"))
      (node (ref "U1") (pin "31") (pinfunction "VSS_1_31") (pintype "power_in"))
      (node (ref "U1") (pin "47") (pinfunction "VSS_2_47") (pintype "power_in"))
      (node (ref "U1") (pin "63") (pinfunction "VSS_3_63") (pintype "power_in"))
      (node (ref "U44") (pin "5") (pinfunction "GND_5") (pintype "passive"))
      (node (ref "U45") (pin "5") (pinfunction "GND_5") (pintype "passive"))
      (node (ref "U8") (pin "2") (pinfunction "GND_2") (pintype "passive"))
      (node (ref "USB") (pin "4") (pinfunction "GND_4") (pintype "passive"))
      (node (ref "X1") (pin "2") (pinfunction "GND_2") (pintype "passive"))
    )
    (net (code "88") (name "GUARD") (class "Default")
      (node (ref "FORCE_H") (pin "2") (pinfunction "Y_2") (pintype "passive"))
      (node (ref "GUARD") (pin "1") (pinfunction "X_1") (pintype "passive"))
      (node (ref "R28") (pin "2") (pinfunction "2_2") (pintype "passive"))
      (node (ref "SENSE_H") (pin "2") (pinfunction "Y_2") (pintype "passive"))
    )
    (net (code "89") (name "Net-(C21-Pad1)") (class "Default")
      (node (ref "C21") (pin "1") (pinfunction "1_1") (pintype "passive"))
      (node (ref "R16") (pin "2") (pinfunction "2_2") (pintype "passive"))
    )
    (net (code "90") (name "Net-(C70-Pad2)") (class "Default")
      (node (ref "C70") (pin "2") (pinfunction "2_2") (pintype "passive"))
      (node (ref "K1") (pin "4") (pinfunction "4_4") (pintype "passive"))
      (node (ref "R31") (pin "2") (pinfunction "2_2") (pintype "passive"))
    )
    (net (code "91") (name "Net-(C71-Pad2)") (class "Default")
      (node (ref "C71") (pin "2") (pinfunction "2_2") (pintype "passive"))
      (node (ref "K2") (pin "4") (pinfunction "4_4") (pintype "passive"))
      (node (ref "R32") (pin "2") (pinfunction "2_2") (pintype "passive"))
    )
    (net (code "92") (name "Net-(C72-Pad2)") (class "Default")
      (node (ref "C72") (pin "2") (pinfunction "2_2") (pintype "passive"))
      (node (ref "K3") (pin "4") (pinfunction "4_4") (pintype "passive"))
      (node (ref "R33") (pin "2") (pinfunction "2_2") (pintype "passive"))
    )
    (net (code "93") (name "Net-(C73-Pad2)") (class "Default")
      (node (ref "C73") (pin "2") (pinfunction "2_2") (pintype "passive"))
      (node (ref "K4") (pin "4") (pinfunction "4_4") (pintype "passive"))
      (node (ref "R34") (pin "2") (pinfunction "2_2") (pintype "passive"))
    )
    (net (code "94") (name "Net-(C74-Pad2)") (class "Default")
      (node (ref "C74") (pin "2") (pinfunction "2_2") (pintype "passive"))
      (node (ref "K5") (pin "4") (pinfunction "4_4") (pintype "passive"))
      (node (ref "R35") (pin "2") (pinfunction "2_2") (pintype "passive"))
    )
    (net (code "95") (name "Net-(C75-Pad2)") (class "Default")
      (node (ref "C75") (pin "2") (pinfunction "2_2") (pintype "passive"))
      (node (ref "K6") (pin "4") (pinfunction "4_4") (pintype "passive"))
      (node (ref "R36") (pin "2") (pinfunction "2_2") (pintype "passive"))
    )
    (net (code "96") (name "Net-(C76-Pad2)") (class "Default")
      (node (ref "C76") (pin "2") (pinfunction "2_2") (pintype "passive"))
      (node (ref "K7") (pin "4") (pinfunction "4_4") (pintype "passive"))
      (node (ref "R37") (pin "2") (pinfunction "2_2") (pintype "passive"))
    )
    (net (code "97") (name "Net-(C77-Pad2)") (class "Default")
      (node (ref "C77") (pin "2") (pinfunction "2_2") (pintype "passive"))
      (node (ref "K8") (pin "4") (pinfunction "4_4") (pintype "passive"))
      (node (ref "R38") (pin "2") (pinfunction "2_2") (pintype "passive"))
    )
    (net (code "98") (name "Net-(C78-Pad2)") (class "Default")
      (node (ref "C78") (pin "2") (pinfunction "2_2") (pintype "passive"))
      (node (ref "K9") (pin "4") (pinfunction "4_4") (pintype "passive"))
      (node (ref "R39") (pin "2") (pinfunction "2_2") (pintype "passive"))
    )
    (net (code "99") (name "Net-(C79-Pad2)") (class "Default")
      (node (ref "C79") (pin "2") (pinfunction "2_2") (pintype "passive"))
      (node (ref "K10") (pin "4") (pinfunction "4_4") (pintype "passive"))
      (node (ref "R40") (pin "2") (pinfunction "2_2") (pintype "passive"))
    )
    (net (code "100") (name "Net-(J1-Pad5)") (class "Default")
      (node (ref "J1") (pin "5") (pinfunction "5_5") (pintype "passive"))
      (node (ref "R66") (pin "2") (pinfunction "2_2") (pintype "passive"))
    )
    (net (code "101") (name "Net-(K1-Pad3)") (class "Default")
      (node (ref "K1") (pin "3") (pinfunction "3_3") (pintype "passive"))
      (node (ref "K1") (pin "6") (pinfunction "6_6") (pintype "passive"))
    )
    (net (code "102") (name "Net-(K2-Pad3)") (class "Default")
      (node (ref "K2") (pin "3") (pinfunction "3_3") (pintype "passive"))
      (node (ref "K2") (pin "6") (pinfunction "6_6") (pintype "passive"))
    )
    (net (code "103") (name "Net-(K3-Pad3)") (class "Default")
      (node (ref "K3") (pin "3") (pinfunction "3_3") (pintype "passive"))
      (node (ref "K3") (pin "6") (pinfunction "6_6") (pintype "passive"))
    )
    (net (code "104") (name "Net-(K4-Pad3)") (class "Default")
      (node (ref "K4") (pin "3") (pinfunction "3_3") (pintype "passive"))
      (node (ref "K4") (pin "6") (pinfunction "6_6") (pintype "passive"))
    )
    (net (code "105") (name "Net-(K5-Pad3)") (class "Default")
      (node (ref "K5") (pin "3") (pinfunction "3_3") (pintype "passive"))
      (node (ref "K5") (pin "6") (pinfunction "6_6") (pintype "passive"))
    )
    (net (code "106") (name "Net-(K6-Pad3)") (class "Default")
      (node (ref "K6") (pin "3") (pinfunction "3_3") (pintype "passive"))
      (node (ref "K6") (pin "6") (pinfunction "6_6") (pintype "passive"))
    )
    (net (code "107") (name "Net-(K7-Pad3)") (class "Default")
      (node (ref "K7") (pin "3") (pinfunction "3_3") (pintype "passive"))
      (node (ref "K7") (pin "6") (pinfunction "6_6") (pintype "passive"))
    )
    (net (code "108") (name "Net-(K8-Pad3)") (class "Default")
      (node (ref "K8") (pin "3") (pinfunction "3_3") (pintype "passive"))
      (node (ref "K8") (pin "6") (pinfunction "6_6") (pintype "passive"))
    )
    (net (code "109") (name "Net-(K9-Pad3)") (class "Default")
      (node (ref "K9") (pin "3") (pinfunction "3_3") (pintype "passive"))
      (node (ref "K9") (pin "6") (pinfunction "6_6") (pintype "passive"))
    )
    (net (code "110") (name "Net-(K10-Pad3)") (class "Default")
      (node (ref "K10") (pin "3") (pinfunction "3_3") (pintype "passive"))
      (node (ref "K10") (pin "6") (pinfunction "6_6") (pintype "passive"))
    )
    (net (code "111") (name "Net-(K11-Pad4)") (class "Default")
      (node (ref "K11") (pin "4") (pintype "passive"))
      (node (ref "R52") (pin "1") (pinfunction "1_1") (pintype "passive"))
    )
    (net (code "112") (name "Net-(K12-Pad4)") (class "Default")
      (node (ref "K12") (pin "4") (pintype "passive"))
      (node (ref "R50") (pin "1") (pinfunction "1_1") (pintype "passive"))
    )
    (net (code "113") (name "Net-(L1-Pad1)") (class "Default")
      (node (ref "L1") (pin "1") (pinfunction "1_1") (pintype "passive"))
      (node (ref "USB") (pin "5") (pinfunction "VSS_5") (pintype "passive"))
      (node (ref "USB") (pin "6") (pinfunction "VSS_6") (pintype "passive"))
    )
    (net (code "114") (name "Net-(LED0-Pad1)") (class "Default")
      (node (ref "LED0") (pin "1") (pinfunction "1_1") (pintype "passive"))
      (node (ref "R68") (pin "1") (pinfunction "1_1") (pintype "passive"))
    )
    (net (code "115") (name "Net-(LED1-Pad1)") (class "Default")
      (node (ref "LED1") (pin "1") (pinfunction "1_1") (pintype "passive"))
      (node (ref "R69") (pin "1") (pinfunction "1_1") (pintype "passive"))
    )
    (net (code "116") (name "Net-(U1-BOOT0)") (class "Default")
      (node (ref "R2") (pin "1") (pinfunction "1_1") (pintype "passive"))
      (node (ref "U1") (pin "60") (pinfunction "BOOT0_60") (pintype "input"))
    )
    (net (code "117") (name "Net-(U1-OSC_IN{slash}PD0)") (class "Default")
      (node (ref "U1") (pin "5") (pinfunction "OSC_IN/PD0_5") (pintype "input"))
      (node (ref "X1") (pin "1") (pinfunction "OSC1_1") (pintype "passive"))
    )
    (net (code "118") (name "Net-(U1-OSC_OUT{slash}PD1)") (class "Default")
      (node (ref "R1") (pin "2") (pinfunction "2_2") (pintype "passive"))
      (node (ref "U1") (pin "6") (pinfunction "OSC_OUT/PD1_6") (pintype "output"))
    )
    (net (code "119") (name "Net-(U2-BW)") (class "Default")
      (node (ref "R27") (pin "2") (pinfunction "2_2") (pintype "passive"))
      (node (ref "U2") (pin "1") (pinfunction "BW_1") (pintype "passive"))
    )
    (net (code "120") (name "Net-(U2-Vin)") (class "Default")
      (node (ref "R16") (pin "1") (pinfunction "1_1") (pintype "passive"))
      (node (ref "R18") (pin "2") (pinfunction "2_2") (pintype "passive"))
      (node (ref "U2") (pin "2") (pinfunction "Vin_2") (pintype "passive"))
    )
    (net (code "121") (name "Net-(U4-+IN_A)") (class "Default")
      (node (ref "C89") (pin "1") (pinfunction "1_1") (pintype "passive"))
      (node (ref "R17") (pin "1") (pinfunction "1_1") (pintype "passive"))
      (node (ref "U4") (pin "3") (pinfunction "+IN_A_3") (pintype "passive"))
    )
    (net (code "122") (name "Net-(U4--IN_A)") (class "Default")
      (node (ref "C20") (pin "1") (pinfunction "1_1") (pintype "passive"))
      (node (ref "K13") (pin "3") (pintype "passive"))
      (node (ref "U4") (pin "2") (pinfunction "-IN_A_2") (pintype "passive"))
    )
    (net (code "123") (name "Net-(U4--IN_B)") (class "Default")
      (node (ref "R28") (pin "1") (pinfunction "1_1") (pintype "passive"))
      (node (ref "U4") (pin "6") (pinfunction "-IN_B_6") (pintype "passive"))
      (node (ref "U4") (pin "7") (pinfunction "Out_B_7") (pintype "passive"))
    )
    (net (code "124") (name "Net-(U4-Out_A)") (class "Default")
      (node (ref "C20") (pin "2") (pinfunction "2_2") (pintype "passive"))
      (node (ref "C89") (pin "2") (pinfunction "2_2") (pintype "passive"))
      (node (ref "R18") (pin "1") (pinfunction "1_1") (pintype "passive"))
      (node (ref "U4") (pin "1") (pinfunction "Out_A_1") (pintype "passive"))
    )
    (net (code "125") (name "Net-(U6-+IN_A)") (class "Default")
      (node (ref "R21") (pin "1") (pinfunction "1_1") (pintype "passive"))
      (node (ref "U6") (pin "3") (pinfunction "+IN_A_3") (pintype "passive"))
    )
    (net (code "126") (name "Net-(U6-+IN_B)") (class "Default")
      (node (ref "R19") (pin "1") (pinfunction "1_1") (pintype "passive"))
      (node (ref "U6") (pin "5") (pinfunction "+IN_B_5") (pintype "passive"))
    )
    (net (code "127") (name "Net-(U7-+IN_A)") (class "Default")
      (node (ref "R12") (pin "2") (pinfunction "2_2") (pintype "passive"))
      (node (ref "U7") (pin "3") (pinfunction "+IN_A_3") (pintype "passive"))
    )
    (net (code "128") (name "Net-(U7-+IN_B)") (class "Default")
      (node (ref "R14") (pin "2") (pinfunction "2_2") (pintype "passive"))
      (node (ref "U7") (pin "5") (pinfunction "+IN_B_5") (pintype "passive"))
    )
    (net (code "129") (name "Net-(U8-BP)") (class "Default")
      (node (ref "C23") (pin "2") (pinfunction "2_2") (pintype "passive"))
      (node (ref "U8") (pin "4") (pinfunction "BP_4") (pintype "passive"))
    )
    (net (code "130") (name "Net-(U9-IN+)") (class "Default")
      (node (ref "C30") (pin "2") (pinfunction "2_2") (pintype "passive"))
      (node (ref "C32") (pin "1") (pinfunction "1_1") (pintype "passive"))
      (node (ref "R54") (pin "1") (pinfunction "1_1") (pintype "passive"))
      (node (ref "U9") (pin "4") (pinfunction "IN+_4") (pintype "passive"))
    )
    (net (code "131") (name "Net-(U9-IN-)") (class "Default")
      (node (ref "C30") (pin "1") (pinfunction "1_1") (pintype "passive"))
      (node (ref "C31") (pin "2") (pinfunction "2_2") (pintype "passive"))
      (node (ref "R53") (pin "1") (pinfunction "1_1") (pintype "passive"))
      (node (ref "U9") (pin "1") (pinfunction "IN-_1") (pintype "passive"))
    )
    (net (code "132") (name "Net-(U10-IN+)") (class "Default")
      (node (ref "C80") (pin "1") (pinfunction "1_1") (pintype "passive"))
      (node (ref "R30") (pin "2") (pinfunction "2_2") (pintype "passive"))
      (node (ref "U10") (pin "3") (pinfunction "IN+_3") (pintype "passive"))
    )
    (net (code "133") (name "Net-(U11-IN+)") (class "Default")
      (node (ref "C84") (pin "2") (pinfunction "2_2") (pintype "passive"))
      (node (ref "R29") (pin "2") (pinfunction "2_2") (pintype "passive"))
      (node (ref "U11") (pin "3") (pinfunction "IN+_3") (pintype "passive"))
    )
    (net (code "134") (name "Net-(U12-Vout)") (class "Default")
      (node (ref "C90") (pin "2") (pinfunction "2_2") (pintype "passive"))
      (node (ref "U12") (pin "6") (pinfunction "Vout_6") (pintype "passive"))
      (node (ref "U13") (pin "3") (pinfunction "+IN_A_3") (pintype "passive"))
    )
    (net (code "135") (name "Net-(U13-+IN_B)") (class "Default")
      (node (ref "R61") (pin "2") (pinfunction "2_2") (pintype "passive"))
      (node (ref "R62") (pin "1") (pinfunction "1_1") (pintype "passive"))
      (node (ref "U13") (pin "5") (pinfunction "+IN_B_5") (pintype "passive"))
    )
    (net (code "136") (name "Net-(U14-Vref)") (class "Default")
      (node (ref "C49") (pin "1") (pinfunction "1_1") (pintype "passive"))
      (node (ref "U14") (pin "1") (pinfunction "Vref_1") (pintype "passive"))
    )
    (net (code "137") (name "Net-(U17-OUT)") (class "Default")
      (node (ref "R30") (pin "1") (pinfunction "1_1") (pintype "passive"))
      (node (ref "U17") (pin "7") (pinfunction "OUT_7") (pintype "passive"))
    )
    (net (code "138") (name "Net-(U18-OUT)") (class "Default")
      (node (ref "R29") (pin "1") (pinfunction "1_1") (pintype "passive"))
      (node (ref "U18") (pin "7") (pinfunction "OUT_7") (pintype "passive"))
    )
    (net (code "139") (name "Net-(U19-IN+)") (class "Default")
      (node (ref "C34") (pin "2") (pinfunction "2_2") (pintype "passive"))
      (node (ref "C35") (pin "1") (pinfunction "1_1") (pintype "passive"))
      (node (ref "R56") (pin "2") (pinfunction "2_2") (pintype "passive"))
      (node (ref "U19") (pin "4") (pinfunction "IN+_4") (pintype "passive"))
    )
    (net (code "140") (name "Net-(U19-IN-)") (class "Default")
      (node (ref "C33") (pin "2") (pinfunction "2_2") (pintype "passive"))
      (node (ref "C34") (pin "1") (pinfunction "1_1") (pintype "passive"))
      (node (ref "R55") (pin "2") (pinfunction "2_2") (pintype "passive"))
      (node (ref "U19") (pin "1") (pinfunction "IN-_1") (pintype "passive"))
    )
    (net (code "141") (name "Net-(U23-+IN_A)") (class "Default")
      (node (ref "R22") (pin "2") (pinfunction "2_2") (pintype "passive"))
      (node (ref "R23") (pin "2") (pinfunction "2_2") (pintype "passive"))
      (node (ref "U23") (pin "3") (pinfunction "+IN_A_3") (pintype "passive"))
    )
    (net (code "142") (name "Net-(U23--IN_A)") (class "Default")
      (node (ref "C154") (pin "1") (pinfunction "1_1") (pintype "passive"))
      (node (ref "R24") (pin "2") (pinfunction "2_2") (pintype "passive"))
      (node (ref "R25") (pin "1") (pinfunction "1_1") (pintype "passive"))
      (node (ref "U23") (pin "2") (pinfunction "-IN_A_2") (pintype "passive"))
    )
    (net (code "143") (name "Net-(U23--IN_B)") (class "Default")
      (node (ref "U23") (pin "6") (pinfunction "-IN_B_6") (pintype "passive"))
      (node (ref "U23") (pin "7") (pinfunction "Out_B_7") (pintype "passive"))
    )
    (net (code "144") (name "Net-(U44-A)") (class "Default")
      (node (ref "J1") (pin "3") (pinfunction "3_3") (pintype "passive"))
      (node (ref "R100") (pin "2") (pinfunction "2_2") (pintype "passive"))
      (node (ref "R102") (pin "1") (pinfunction "1_1") (pintype "passive"))
      (node (ref "U44") (pin "6") (pinfunction "A_6") (pintype "passive"))
    )
    (net (code "145") (name "Net-(U44-B)") (class "Default")
      (node (ref "J1") (pin "2") (pinfunction "2_2") (pintype "passive"))
      (node (ref "R100") (pin "1") (pinfunction "1_1") (pintype "passive"))
      (node (ref "R101") (pin "1") (pinfunction "1_1") (pintype "passive"))
      (node (ref "U44") (pin "7") (pinfunction "B_7") (pintype "passive"))
    )
    (net (code "146") (name "Net-(U45-A)") (class "Default")
      (node (ref "R103") (pin "2") (pinfunction "2_2") (pintype "passive"))
      (node (ref "R105") (pin "1") (pinfunction "1_1") (pintype "passive"))
      (node (ref "RS485_2") (pin "2") (pinfunction "2_2") (pintype "passive"))
      (node (ref "U45") (pin "6") (pinfunction "A_6") (pintype "passive"))
    )
    (net (code "147") (name "Net-(U45-B)") (class "Default")
      (node (ref "R103") (pin "1") (pinfunction "1_1") (pintype "passive"))
      (node (ref "R104") (pin "1") (pinfunction "1_1") (pintype "passive"))
      (node (ref "RS485_2") (pin "1") (pinfunction "1_1") (pintype "passive"))
      (node (ref "U45") (pin "7") (pinfunction "B_7") (pintype "passive"))
    )
    (net (code "148") (name "Net-(USB-D+)") (class "Default")
      (node (ref "R41") (pin "1") (pinfunction "1_1") (pintype "passive"))
      (node (ref "USB") (pin "3") (pinfunction "D+_3") (pintype "passive"))
    )
    (net (code "149") (name "Net-(USB-D-)") (class "Default")
      (node (ref "R43") (pin "1") (pinfunction "1_1") (pintype "passive"))
      (node (ref "USB") (pin "2") (pinfunction "D-_2") (pintype "passive"))
    )
    (net (code "150") (name "Net-(X1-OSC2)") (class "Default")
      (node (ref "R1") (pin "1") (pinfunction "1_1") (pintype "passive"))
      (node (ref "X1") (pin "3") (pinfunction "OSC2_3") (pintype "passive"))
    )
    (net (code "151") (name "unconnected-(DL-Vcc-Pad1)") (class "Default")
      (node (ref "DL") (pin "1") (pinfunction "Vcc_1") (pintype "passive"))
    )
    (net (code "152") (name "unconnected-(J1-MH1-Pad10)") (class "Default")
      (node (ref "J1") (pin "10") (pinfunction "MH1_10") (pintype "passive"))
    )
    (net (code "153") (name "unconnected-(J1-MH2-Pad11)") (class "Default")
      (node (ref "J1") (pin "11") (pinfunction "MH2_11") (pintype "passive"))
    )
    (net (code "154") (name "unconnected-(J1-Pad1)") (class "Default")
      (node (ref "J1") (pin "1") (pinfunction "1_1") (pintype "passive"))
    )
    (net (code "155") (name "unconnected-(J1-Pad4)") (class "Default")
      (node (ref "J1") (pin "4") (pinfunction "4_4") (pintype "passive"))
    )
    (net (code "156") (name "unconnected-(J1-Pad6)") (class "Default")
      (node (ref "J1") (pin "6") (pinfunction "6_6") (pintype "passive"))
    )
    (net (code "157") (name "unconnected-(J1-Pad7)") (class "Default")
      (node (ref "J1") (pin "7") (pinfunction "7_7") (pintype "passive"))
    )
    (net (code "158") (name "unconnected-(J1-Pad8)") (class "Default")
      (node (ref "J1") (pin "8") (pinfunction "8_8") (pintype "passive"))
    )
    (net (code "159") (name "unconnected-(J1-Pad9)") (class "Default")
      (node (ref "J1") (pin "9") (pinfunction "9_9") (pintype "passive"))
    )
    (net (code "160") (name "unconnected-(K1-Pad2)") (class "Default")
      (node (ref "K1") (pin "2") (pinfunction "2_2") (pintype "passive"))
    )
    (net (code "161") (name "unconnected-(K1-Pad7)") (class "Default")
      (node (ref "K1") (pin "7") (pinfunction "7_7") (pintype "passive"))
    )
    (net (code "162") (name "unconnected-(K2-Pad2)") (class "Default")
      (node (ref "K2") (pin "2") (pinfunction "2_2") (pintype "passive"))
    )
    (net (code "163") (name "unconnected-(K2-Pad7)") (class "Default")
      (node (ref "K2") (pin "7") (pinfunction "7_7") (pintype "passive"))
    )
    (net (code "164") (name "unconnected-(K3-Pad2)") (class "Default")
      (node (ref "K3") (pin "2") (pinfunction "2_2") (pintype "passive"))
    )
    (net (code "165") (name "unconnected-(K3-Pad7)") (class "Default")
      (node (ref "K3") (pin "7") (pinfunction "7_7") (pintype "passive"))
    )
    (net (code "166") (name "unconnected-(K4-Pad2)") (class "Default")
      (node (ref "K4") (pin "2") (pinfunction "2_2") (pintype "passive"))
    )
    (net (code "167") (name "unconnected-(K4-Pad7)") (class "Default")
      (node (ref "K4") (pin "7") (pinfunction "7_7") (pintype "passive"))
    )
    (net (code "168") (name "unconnected-(K5-Pad2)") (class "Default")
      (node (ref "K5") (pin "2") (pinfunction "2_2") (pintype "passive"))
    )
    (net (code "169") (name "unconnected-(K5-Pad7)") (class "Default")
      (node (ref "K5") (pin "7") (pinfunction "7_7") (pintype "passive"))
    )
    (net (code "170") (name "unconnected-(K6-Pad2)") (class "Default")
      (node (ref "K6") (pin "2") (pinfunction "2_2") (pintype "passive"))
    )
    (net (code "171") (name "unconnected-(K6-Pad7)") (class "Default")
      (node (ref "K6") (pin "7") (pinfunction "7_7") (pintype "passive"))
    )
    (net (code "172") (name "unconnected-(K7-Pad2)") (class "Default")
      (node (ref "K7") (pin "2") (pinfunction "2_2") (pintype "passive"))
    )
    (net (code "173") (name "unconnected-(K7-Pad7)") (class "Default")
      (node (ref "K7") (pin "7") (pinfunction "7_7") (pintype "passive"))
    )
    (net (code "174") (name "unconnected-(K8-Pad2)") (class "Default")
      (node (ref "K8") (pin "2") (pinfunction "2_2") (pintype "passive"))
    )
    (net (code "175") (name "unconnected-(K8-Pad7)") (class "Default")
      (node (ref "K8") (pin "7") (pinfunction "7_7") (pintype "passive"))
    )
    (net (code "176") (name "unconnected-(K9-Pad2)") (class "Default")
      (node (ref "K9") (pin "2") (pinfunction "2_2") (pintype "passive"))
    )
    (net (code "177") (name "unconnected-(K9-Pad7)") (class "Default")
      (node (ref "K9") (pin "7") (pinfunction "7_7") (pintype "passive"))
    )
    (net (code "178") (name "unconnected-(K10-Pad2)") (class "Default")
      (node (ref "K10") (pin "2") (pinfunction "2_2") (pintype "passive"))
    )
    (net (code "179") (name "unconnected-(K10-Pad7)") (class "Default")
      (node (ref "K10") (pin "7") (pinfunction "7_7") (pintype "passive"))
    )
    (net (code "180") (name "unconnected-(K11-Pad1)") (class "Default")
      (node (ref "K11") (pin "1") (pintype "passive"))
    )
    (net (code "181") (name "unconnected-(K11-Pad3)") (class "Default")
      (node (ref "K11") (pin "3") (pintype "passive"))
    )
    (net (code "182") (name "unconnected-(K12-Pad1)") (class "Default")
      (node (ref "K12") (pin "1") (pintype "passive"))
    )
    (net (code "183") (name "unconnected-(K12-Pad3)") (class "Default")
      (node (ref "K12") (pin "3") (pintype "passive"))
    )
    (net (code "184") (name "unconnected-(K13-Pad4)") (class "Default")
      (node (ref "K13") (pin "4") (pintype "passive"))
    )
    (net (code "185") (name "unconnected-(K14-Pad3)") (class "Default")
      (node (ref "K14") (pin "3") (pintype "passive"))
    )
    (net (code "186") (name "unconnected-(LCD-Pad6)") (class "Default")
      (node (ref "LCD") (pin "6") (pinfunction "6_6") (pintype "passive+no_connect"))
    )
    (net (code "187") (name "unconnected-(U1-NRST-Pad7)") (class "Default")
      (node (ref "U1") (pin "7") (pinfunction "NRST_7") (pintype "bidirectional"))
    )
    (net (code "188") (name "unconnected-(U1-PC14-OSC32_IN-Pad3)") (class "Default")
      (node (ref "U1") (pin "3") (pinfunction "PC14-OSC32_IN_3") (pintype "bidirectional"))
    )
    (net (code "189") (name "unconnected-(U1-PC15-OSC32_OUT-Pad4)") (class "Default")
      (node (ref "U1") (pin "4") (pinfunction "PC15-OSC32_OUT_4") (pintype "bidirectional"))
    )
    (net (code "190") (name "unconnected-(U9-Rg-Pad2)") (class "Default")
      (node (ref "U9") (pin "2") (pinfunction "Rg_2") (pintype "passive"))
    )
    (net (code "191") (name "unconnected-(U9-Rg-Pad3)") (class "Default")
      (node (ref "U9") (pin "3") (pinfunction "Rg_3") (pintype "passive"))
    )
    (net (code "192") (name "unconnected-(U12-NC-Pad3)") (class "Default")
      (node (ref "U12") (pin "3") (pinfunction "NC_3") (pintype "passive+no_connect"))
    )
    (net (code "193") (name "unconnected-(U12-NC-Pad7)") (class "Default")
      (node (ref "U12") (pin "7") (pinfunction "NC_7") (pintype "passive+no_connect"))
    )
    (net (code "194") (name "unconnected-(U12-TP-Pad1)") (class "Default")
      (node (ref "U12") (pin "1") (pinfunction "TP_1") (pintype "passive"))
    )
    (net (code "195") (name "unconnected-(U12-TP-Pad8)") (class "Default")
      (node (ref "U12") (pin "8") (pinfunction "TP_8") (pintype "passive"))
    )
    (net (code "196") (name "unconnected-(U12-TRIM-Pad5)") (class "Default")
      (node (ref "U12") (pin "5") (pinfunction "TRIM_5") (pintype "passive+no_connect"))
    )
    (net (code "197") (name "unconnected-(U14-NC-Pad2)") (class "Default")
      (node (ref "U14") (pin "2") (pinfunction "NC_2") (pintype "passive+no_connect"))
    )
    (net (code "198") (name "unconnected-(U14-NC-Pad6)") (class "Default")
      (node (ref "U14") (pin "6") (pinfunction "NC_6") (pintype "passive+no_connect"))
    )
    (net (code "199") (name "unconnected-(U14-SDO-Pad8)") (class "Default")
      (node (ref "U14") (pin "8") (pinfunction "SDO_8") (pintype "passive+no_connect"))
    )
    (net (code "200") (name "unconnected-(U19-Rg-Pad2)") (class "Default")
      (node (ref "U19") (pin "2") (pinfunction "Rg_2") (pintype "passive"))
    )
    (net (code "201") (name "unconnected-(U19-Rg-Pad3)") (class "Default")
      (node (ref "U19") (pin "3") (pinfunction "Rg_3") (pintype "passive"))
    )
    (net (code "202") (name "unconnected-(USB-Vcc-Pad1)") (class "Default")
      (node (ref "USB") (pin "1") (pinfunction "Vcc_1") (pintype "passive"))
    )
  )
)
